# regulator_plus_switch_multi.net
KiCad netlist of a schematic drawn in EAGLE
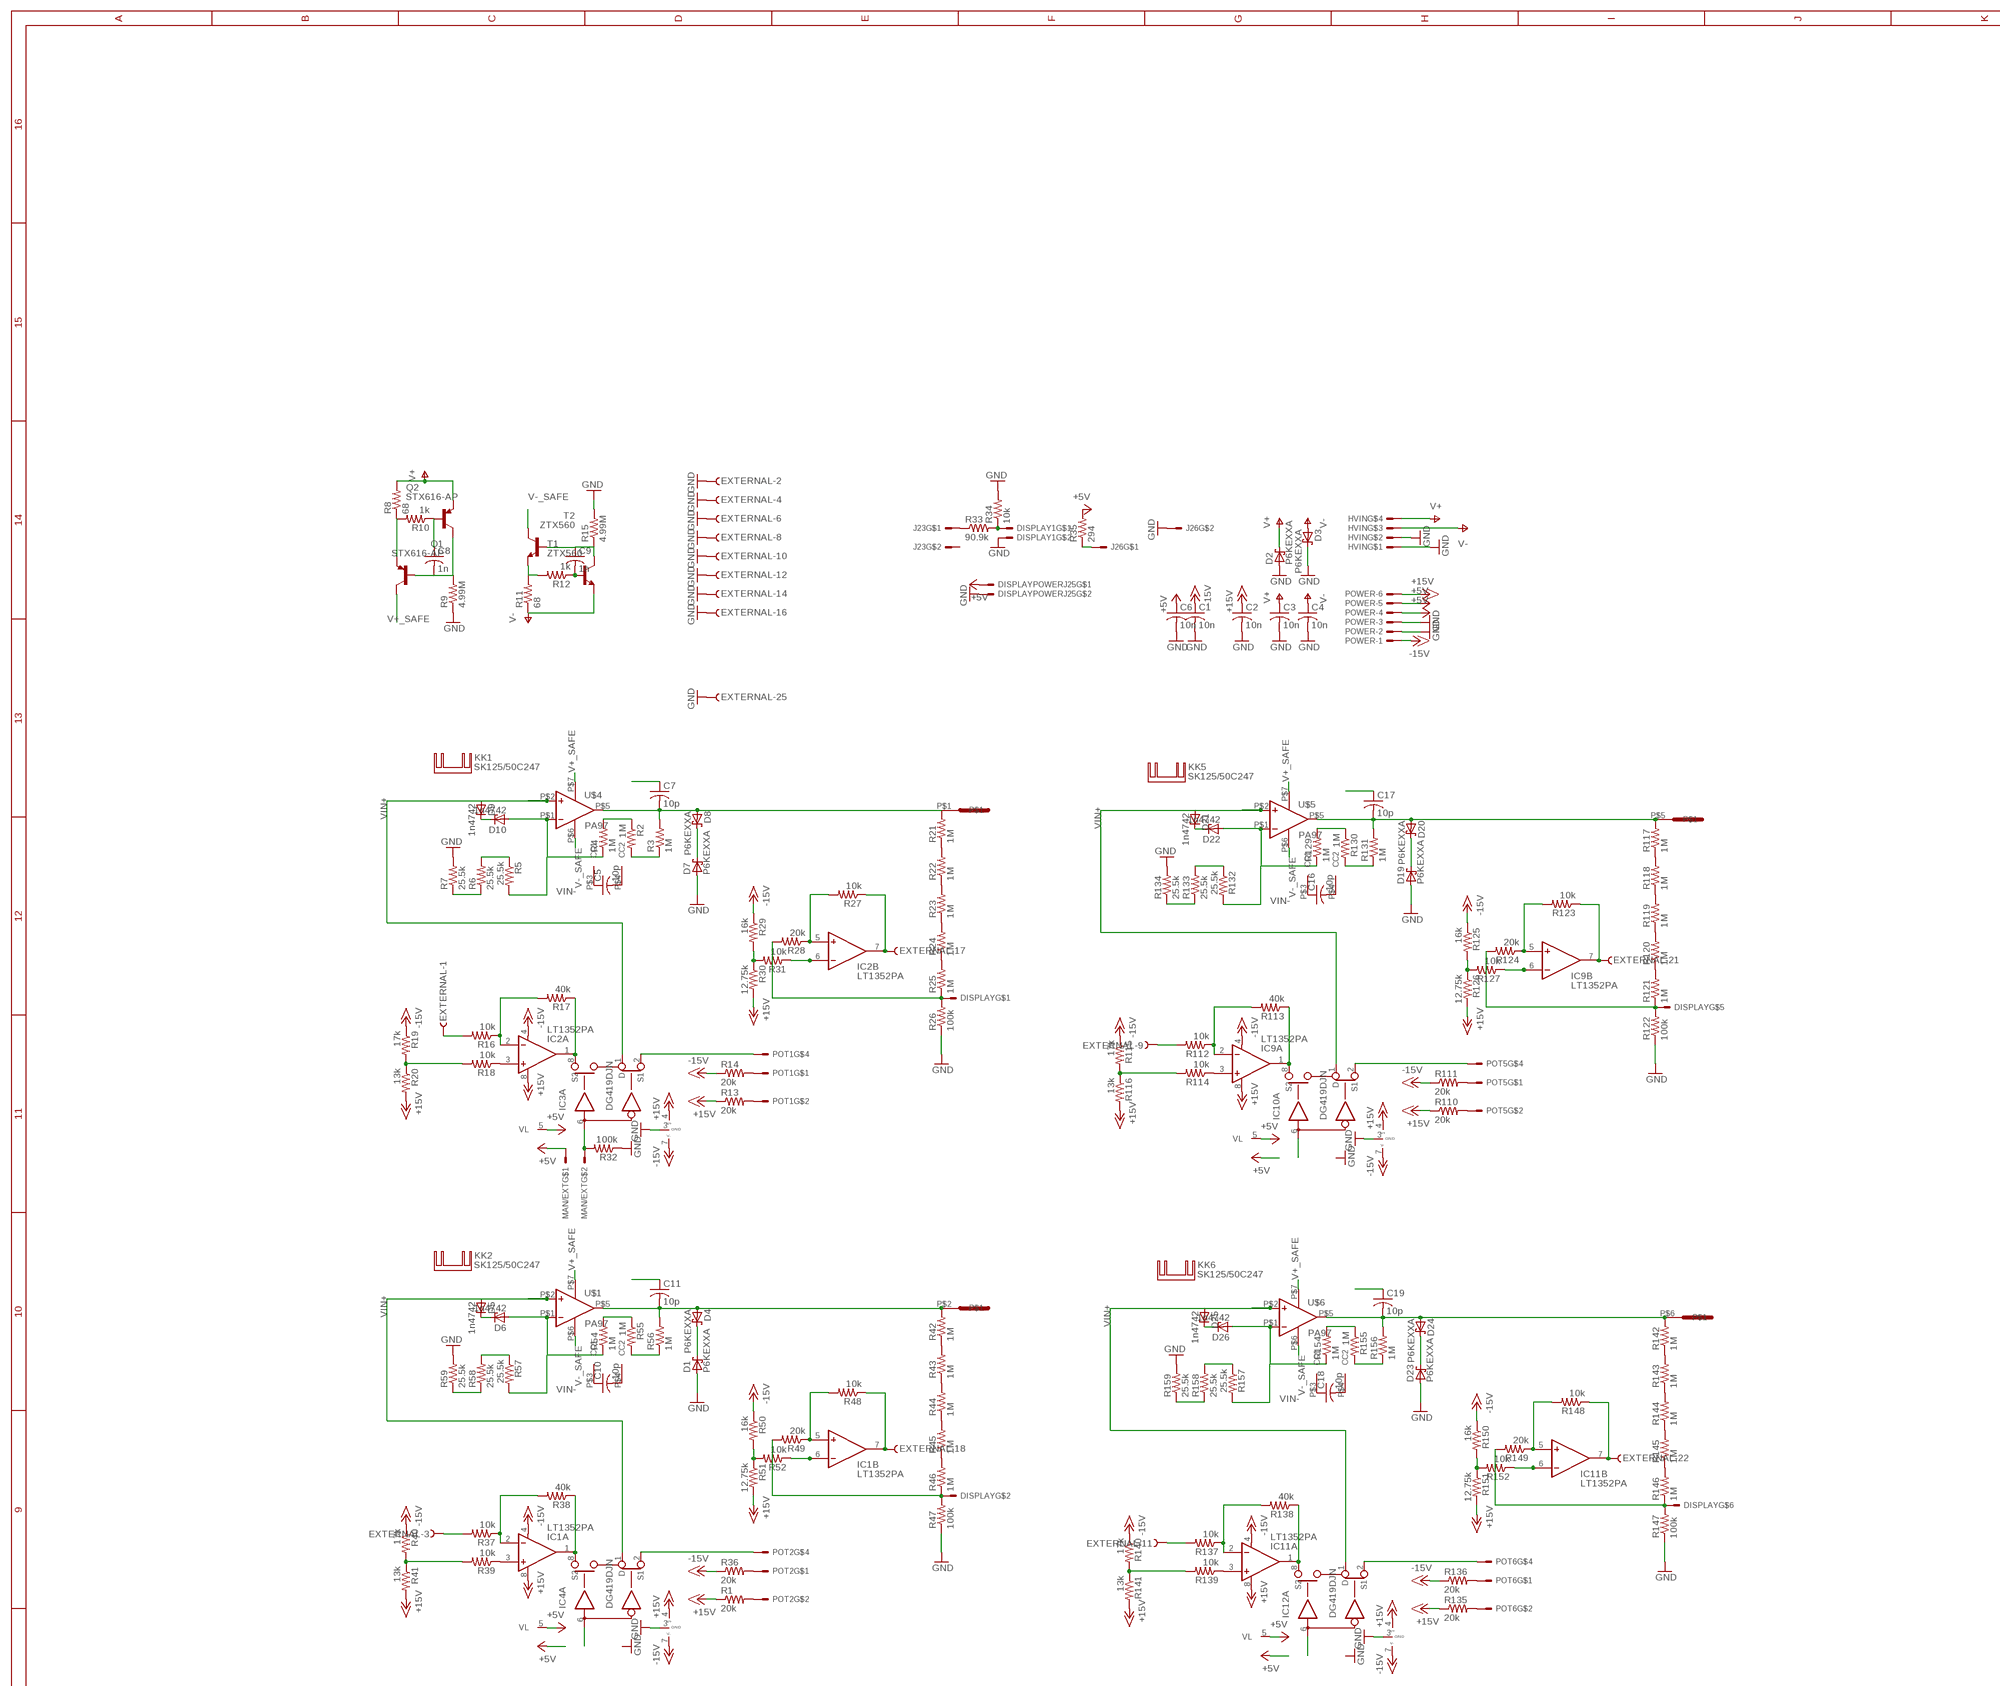
[diagram p0: schematic, sheet 1, part 1 of 2]
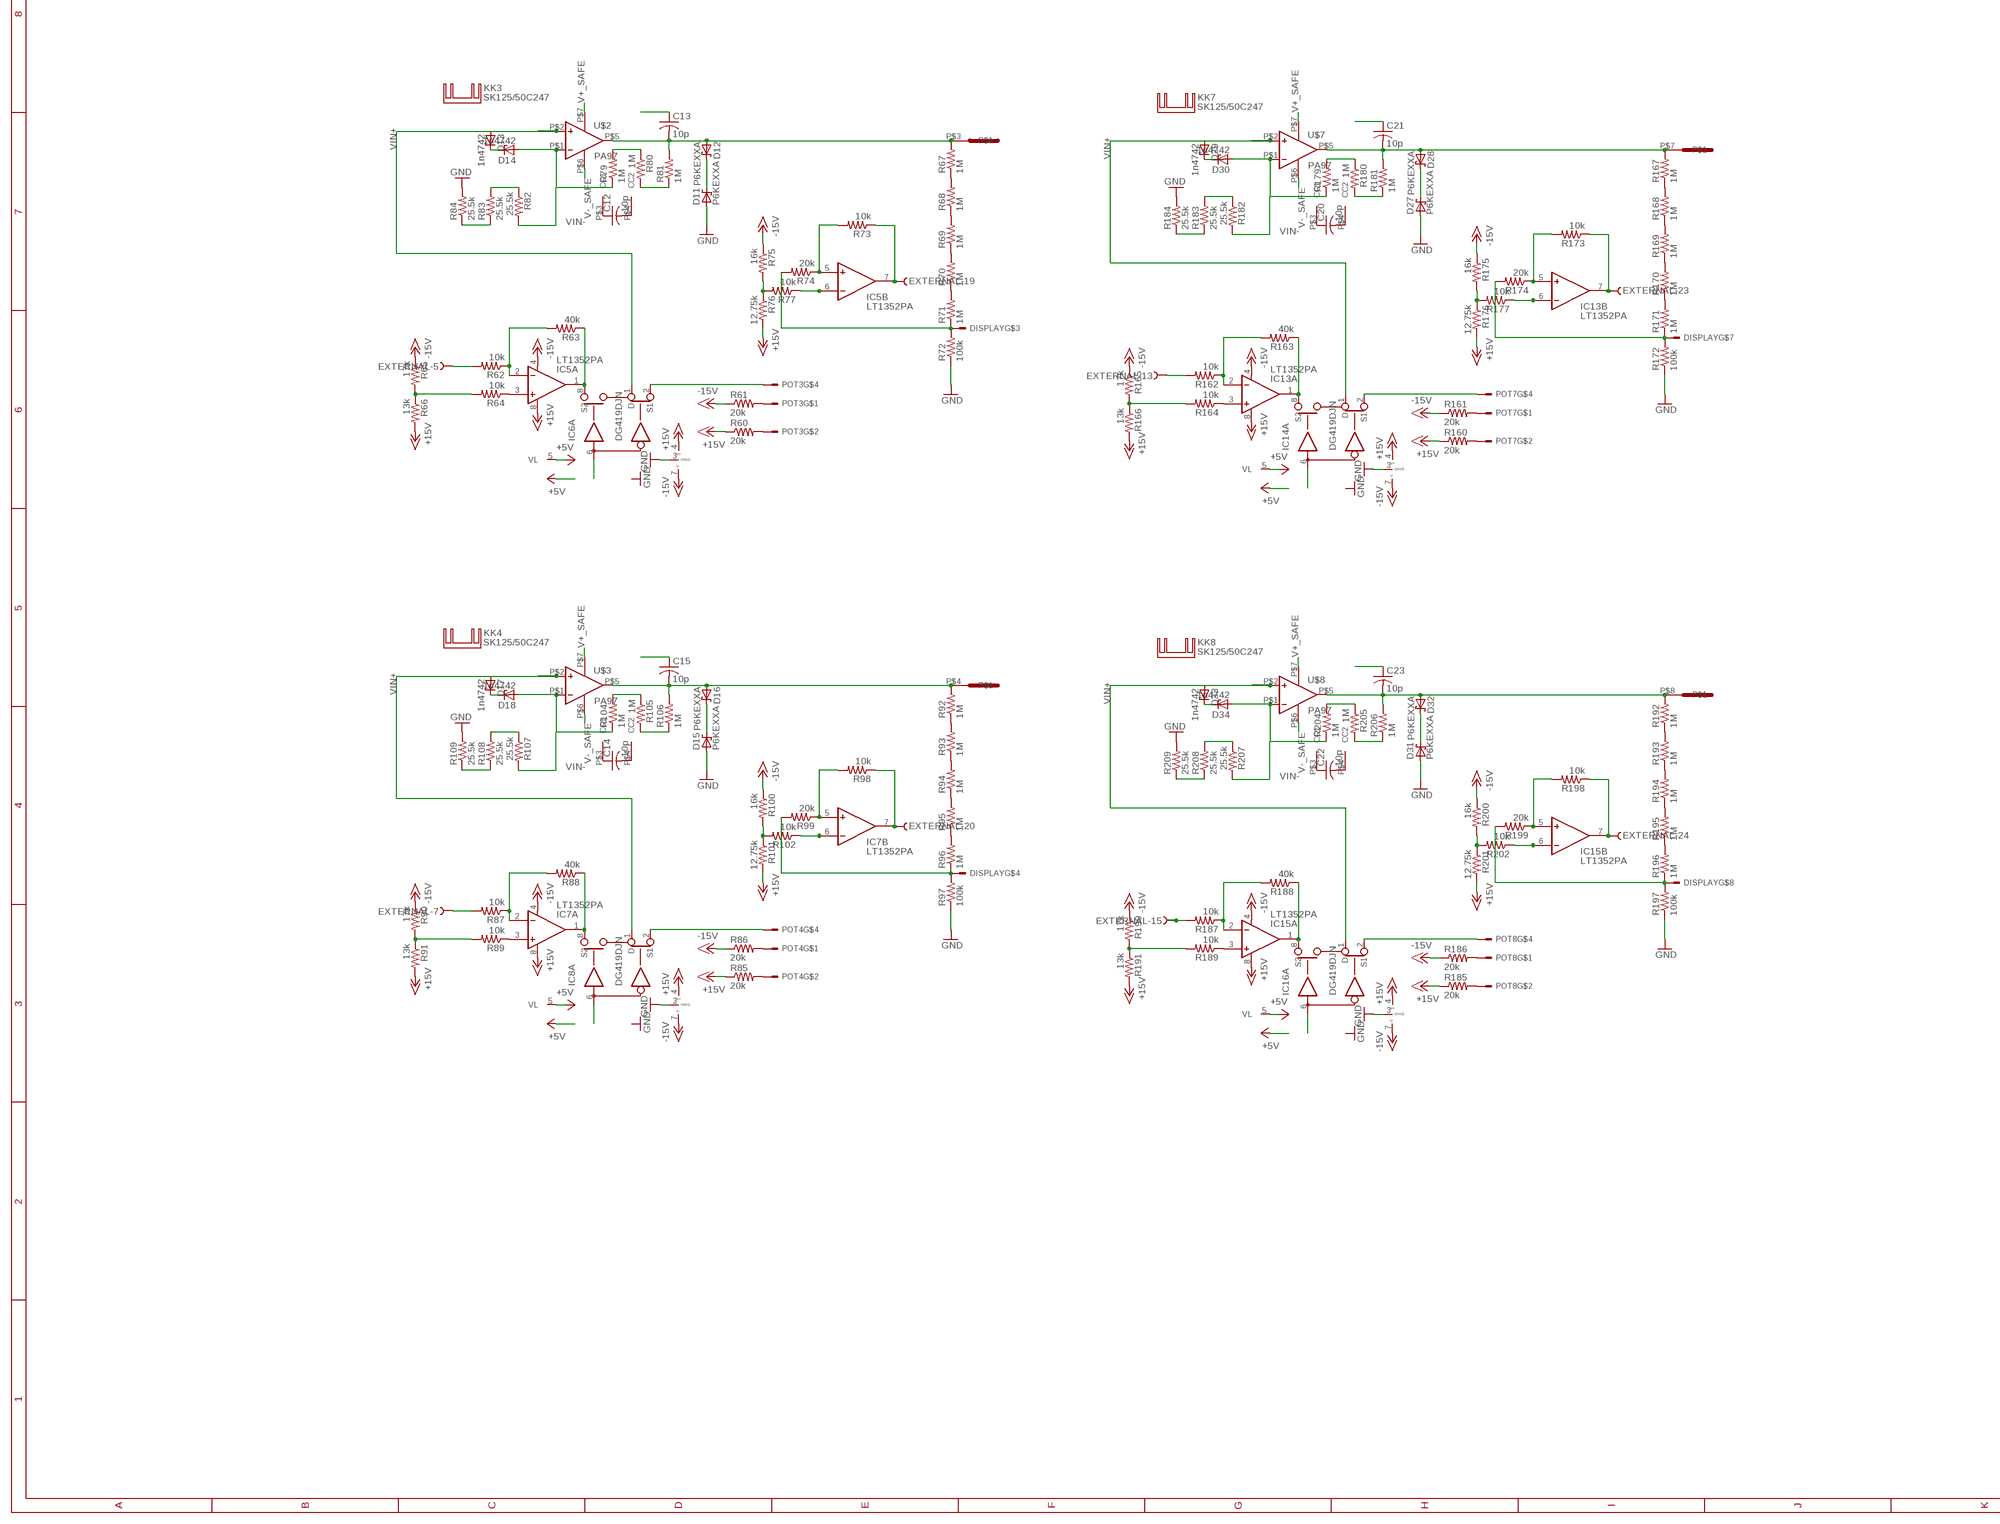
[diagram p1: schematic, sheet 1, part 2 of 2]

(export (version "E")
  (design (tool "Eeschema 10.0.6"))
  (components
    (comp (ref "C1")
      (value "10n")
      (footprint "eagle-import:C075-032X103")
      (libsource (lib "eagle-import") (part "C-US075-032X103"))
    )
    (comp (ref "C2")
      (value "10n")
      (footprint "eagle-import:C075-032X103")
      (libsource (lib "eagle-import") (part "C-US075-032X103"))
    )
    (comp (ref "C3")
      (value "10n")
      (footprint "eagle-import:C075-032X103")
      (libsource (lib "eagle-import") (part "C-US075-032X103"))
    )
    (comp (ref "C4")
      (value "10n")
      (footprint "eagle-import:C075-032X103")
      (libsource (lib "eagle-import") (part "C-US075-032X103"))
    )
    (comp (ref "C5")
      (value "10p")
      (footprint "eagle-import:C075-032X103")
      (libsource (lib "eagle-import") (part "C-US075-032X103"))
    )
    (comp (ref "C6")
      (value "10n")
      (footprint "eagle-import:C075-032X103")
      (libsource (lib "eagle-import") (part "C-US075-032X103"))
    )
    (comp (ref "C7")
      (value "10p")
      (footprint "eagle-import:C075-032X103")
      (libsource (lib "eagle-import") (part "C-US075-032X103"))
    )
    (comp (ref "C8")
      (value "1n")
      (footprint "eagle-import:C075-032X103")
      (libsource (lib "eagle-import") (part "C-US075-032X103"))
    )
    (comp (ref "C9")
      (value "1n")
      (footprint "eagle-import:C075-032X103")
      (libsource (lib "eagle-import") (part "C-US075-032X103"))
    )
    (comp (ref "C10")
      (value "10p")
      (footprint "eagle-import:C075-032X103")
      (libsource (lib "eagle-import") (part "C-US075-032X103"))
    )
    (comp (ref "C11")
      (value "10p")
      (footprint "eagle-import:C075-032X103")
      (libsource (lib "eagle-import") (part "C-US075-032X103"))
    )
    (comp (ref "C12")
      (value "10p")
      (footprint "eagle-import:C075-032X103")
      (libsource (lib "eagle-import") (part "C-US075-032X103"))
    )
    (comp (ref "C13")
      (value "10p")
      (footprint "eagle-import:C075-032X103")
      (libsource (lib "eagle-import") (part "C-US075-032X103"))
    )
    (comp (ref "C14")
      (value "10p")
      (footprint "eagle-import:C075-032X103")
      (libsource (lib "eagle-import") (part "C-US075-032X103"))
    )
    (comp (ref "C15")
      (value "10p")
      (footprint "eagle-import:C075-032X103")
      (libsource (lib "eagle-import") (part "C-US075-032X103"))
    )
    (comp (ref "C16")
      (value "10p")
      (footprint "eagle-import:C075-032X103")
      (libsource (lib "eagle-import") (part "C-US075-032X103"))
    )
    (comp (ref "C17")
      (value "10p")
      (footprint "eagle-import:C075-032X103")
      (libsource (lib "eagle-import") (part "C-US075-032X103"))
    )
    (comp (ref "C18")
      (value "10p")
      (footprint "eagle-import:C075-032X103")
      (libsource (lib "eagle-import") (part "C-US075-032X103"))
    )
    (comp (ref "C19")
      (value "10p")
      (footprint "eagle-import:C075-032X103")
      (libsource (lib "eagle-import") (part "C-US075-032X103"))
    )
    (comp (ref "C20")
      (value "10p")
      (footprint "eagle-import:C075-032X103")
      (libsource (lib "eagle-import") (part "C-US075-032X103"))
    )
    (comp (ref "C21")
      (value "10p")
      (footprint "eagle-import:C075-032X103")
      (libsource (lib "eagle-import") (part "C-US075-032X103"))
    )
    (comp (ref "C22")
      (value "10p")
      (footprint "eagle-import:C075-032X103")
      (libsource (lib "eagle-import") (part "C-US075-032X103"))
    )
    (comp (ref "C23")
      (value "10p")
      (footprint "eagle-import:C075-032X103")
      (libsource (lib "eagle-import") (part "C-US075-032X103"))
    )
    (comp (ref "D1")
      (value "P6KEXXA")
      (footprint "eagle-import:C1702-15")
      (libsource (lib "eagle-import") (part "P6KEXXA"))
    )
    (comp (ref "D2")
      (value "P6KEXXA")
      (footprint "eagle-import:C1702-15")
      (libsource (lib "eagle-import") (part "P6KEXXA"))
    )
    (comp (ref "D3")
      (value "P6KEXXA")
      (footprint "eagle-import:C1702-15")
      (libsource (lib "eagle-import") (part "P6KEXXA"))
    )
    (comp (ref "D4")
      (value "P6KEXXA")
      (footprint "eagle-import:C1702-15")
      (libsource (lib "eagle-import") (part "P6KEXXA"))
    )
    (comp (ref "D5")
      (value "1n4742")
      (footprint "eagle-import:DO41Z10")
      (libsource (lib "eagle-import") (part "ZENER-DIODEDO41Z10"))
    )
    (comp (ref "D6")
      (value "1n4742")
      (footprint "eagle-import:DO41Z10")
      (libsource (lib "eagle-import") (part "ZENER-DIODEDO41Z10"))
    )
    (comp (ref "D7")
      (value "P6KEXXA")
      (footprint "eagle-import:C1702-15")
      (libsource (lib "eagle-import") (part "P6KEXXA"))
    )
    (comp (ref "D8")
      (value "P6KEXXA")
      (footprint "eagle-import:C1702-15")
      (libsource (lib "eagle-import") (part "P6KEXXA"))
    )
    (comp (ref "D9")
      (value "1n4742")
      (footprint "eagle-import:DO41Z10")
      (libsource (lib "eagle-import") (part "ZENER-DIODEDO41Z10"))
    )
    (comp (ref "D10")
      (value "1n4742")
      (footprint "eagle-import:DO41Z10")
      (libsource (lib "eagle-import") (part "ZENER-DIODEDO41Z10"))
    )
    (comp (ref "D11")
      (value "P6KEXXA")
      (footprint "eagle-import:C1702-15")
      (libsource (lib "eagle-import") (part "P6KEXXA"))
    )
    (comp (ref "D12")
      (value "P6KEXXA")
      (footprint "eagle-import:C1702-15")
      (libsource (lib "eagle-import") (part "P6KEXXA"))
    )
    (comp (ref "D13")
      (value "1n4742")
      (footprint "eagle-import:DO41Z10")
      (libsource (lib "eagle-import") (part "ZENER-DIODEDO41Z10"))
    )
    (comp (ref "D14")
      (value "1n4742")
      (footprint "eagle-import:DO41Z10")
      (libsource (lib "eagle-import") (part "ZENER-DIODEDO41Z10"))
    )
    (comp (ref "D15")
      (value "P6KEXXA")
      (footprint "eagle-import:C1702-15")
      (libsource (lib "eagle-import") (part "P6KEXXA"))
    )
    (comp (ref "D16")
      (value "P6KEXXA")
      (footprint "eagle-import:C1702-15")
      (libsource (lib "eagle-import") (part "P6KEXXA"))
    )
    (comp (ref "D17")
      (value "1n4742")
      (footprint "eagle-import:DO41Z10")
      (libsource (lib "eagle-import") (part "ZENER-DIODEDO41Z10"))
    )
    (comp (ref "D18")
      (value "1n4742")
      (footprint "eagle-import:DO41Z10")
      (libsource (lib "eagle-import") (part "ZENER-DIODEDO41Z10"))
    )
    (comp (ref "D19")
      (value "P6KEXXA")
      (footprint "eagle-import:C1702-15")
      (libsource (lib "eagle-import") (part "P6KEXXA"))
    )
    (comp (ref "D20")
      (value "P6KEXXA")
      (footprint "eagle-import:C1702-15")
      (libsource (lib "eagle-import") (part "P6KEXXA"))
    )
    (comp (ref "D21")
      (value "1n4742")
      (footprint "eagle-import:DO41Z10")
      (libsource (lib "eagle-import") (part "ZENER-DIODEDO41Z10"))
    )
    (comp (ref "D22")
      (value "1n4742")
      (footprint "eagle-import:DO41Z10")
      (libsource (lib "eagle-import") (part "ZENER-DIODEDO41Z10"))
    )
    (comp (ref "D23")
      (value "P6KEXXA")
      (footprint "eagle-import:C1702-15")
      (libsource (lib "eagle-import") (part "P6KEXXA"))
    )
    (comp (ref "D24")
      (value "P6KEXXA")
      (footprint "eagle-import:C1702-15")
      (libsource (lib "eagle-import") (part "P6KEXXA"))
    )
    (comp (ref "D25")
      (value "1n4742")
      (footprint "eagle-import:DO41Z10")
      (libsource (lib "eagle-import") (part "ZENER-DIODEDO41Z10"))
    )
    (comp (ref "D26")
      (value "1n4742")
      (footprint "eagle-import:DO41Z10")
      (libsource (lib "eagle-import") (part "ZENER-DIODEDO41Z10"))
    )
    (comp (ref "D27")
      (value "P6KEXXA")
      (footprint "eagle-import:C1702-15")
      (libsource (lib "eagle-import") (part "P6KEXXA"))
    )
    (comp (ref "D28")
      (value "P6KEXXA")
      (footprint "eagle-import:C1702-15")
      (libsource (lib "eagle-import") (part "P6KEXXA"))
    )
    (comp (ref "D29")
      (value "1n4742")
      (footprint "eagle-import:DO41Z10")
      (libsource (lib "eagle-import") (part "ZENER-DIODEDO41Z10"))
    )
    (comp (ref "D30")
      (value "1n4742")
      (footprint "eagle-import:DO41Z10")
      (libsource (lib "eagle-import") (part "ZENER-DIODEDO41Z10"))
    )
    (comp (ref "D31")
      (value "P6KEXXA")
      (footprint "eagle-import:C1702-15")
      (libsource (lib "eagle-import") (part "P6KEXXA"))
    )
    (comp (ref "D32")
      (value "P6KEXXA")
      (footprint "eagle-import:C1702-15")
      (libsource (lib "eagle-import") (part "P6KEXXA"))
    )
    (comp (ref "D33")
      (value "1n4742")
      (footprint "eagle-import:DO41Z10")
      (libsource (lib "eagle-import") (part "ZENER-DIODEDO41Z10"))
    )
    (comp (ref "D34")
      (value "1n4742")
      (footprint "eagle-import:DO41Z10")
      (libsource (lib "eagle-import") (part "ZENER-DIODEDO41Z10"))
    )
    (comp (ref "DISPLAY")
      (value "5669-8")
      (footprint "eagle-import:5669-8")
      (libsource (lib "eagle-import") (part "5669-8"))
    )
    (comp (ref "DISPLAY1")
      (value "5569-2")
      (footprint "eagle-import:5569-2")
      (libsource (lib "eagle-import") (part "5569-2"))
    )
    (comp (ref "DISPLAYPOWERJ25")
      (value "5569-2")
      (footprint "eagle-import:5569-2")
      (libsource (lib "eagle-import") (part "5569-2"))
    )
    (comp (ref "EXTERNAL")
      (value "F25HPS")
      (footprint "eagle-import:F25HP")
      (libsource (lib "eagle-import") (part "F25?SHP"))
    )
    (comp (ref "HVIN")
      (value "5569-4")
      (footprint "eagle-import:5669-4")
      (libsource (lib "eagle-import") (part "5569-4"))
    )
    (comp (ref "IC1")
      (value "LT1352PA")
      (footprint "eagle-import:DIL08")
      (libsource (lib "eagle-import") (part "LT1352PA"))
    )
    (comp (ref "IC2")
      (value "LT1352PA")
      (footprint "eagle-import:DIL08")
      (libsource (lib "eagle-import") (part "LT1352PA"))
    )
    (comp (ref "IC3")
      (value "DG419DJN")
      (footprint "eagle-import:DIL08")
      (libsource (lib "eagle-import") (part "DG419DJN"))
    )
    (comp (ref "IC4")
      (value "DG419DJN")
      (footprint "eagle-import:DIL08")
      (libsource (lib "eagle-import") (part "DG419DJN"))
    )
    (comp (ref "IC5")
      (value "LT1352PA")
      (footprint "eagle-import:DIL08")
      (libsource (lib "eagle-import") (part "LT1352PA"))
    )
    (comp (ref "IC6")
      (value "DG419DJN")
      (footprint "eagle-import:DIL08")
      (libsource (lib "eagle-import") (part "DG419DJN"))
    )
    (comp (ref "IC7")
      (value "LT1352PA")
      (footprint "eagle-import:DIL08")
      (libsource (lib "eagle-import") (part "LT1352PA"))
    )
    (comp (ref "IC8")
      (value "DG419DJN")
      (footprint "eagle-import:DIL08")
      (libsource (lib "eagle-import") (part "DG419DJN"))
    )
    (comp (ref "IC9")
      (value "LT1352PA")
      (footprint "eagle-import:DIL08")
      (libsource (lib "eagle-import") (part "LT1352PA"))
    )
    (comp (ref "IC10")
      (value "DG419DJN")
      (footprint "eagle-import:DIL08")
      (libsource (lib "eagle-import") (part "DG419DJN"))
    )
    (comp (ref "IC11")
      (value "LT1352PA")
      (footprint "eagle-import:DIL08")
      (libsource (lib "eagle-import") (part "LT1352PA"))
    )
    (comp (ref "IC12")
      (value "DG419DJN")
      (footprint "eagle-import:DIL08")
      (libsource (lib "eagle-import") (part "DG419DJN"))
    )
    (comp (ref "IC13")
      (value "LT1352PA")
      (footprint "eagle-import:DIL08")
      (libsource (lib "eagle-import") (part "LT1352PA"))
    )
    (comp (ref "IC14")
      (value "DG419DJN")
      (footprint "eagle-import:DIL08")
      (libsource (lib "eagle-import") (part "DG419DJN"))
    )
    (comp (ref "IC15")
      (value "LT1352PA")
      (footprint "eagle-import:DIL08")
      (libsource (lib "eagle-import") (part "LT1352PA"))
    )
    (comp (ref "IC16")
      (value "DG419DJN")
      (footprint "eagle-import:DIL08")
      (libsource (lib "eagle-import") (part "DG419DJN"))
    )
    (comp (ref "J23")
      (value "5569-2")
      (footprint "eagle-import:5569-2")
      (libsource (lib "eagle-import") (part "5569-2"))
    )
    (comp (ref "J26")
      (value "5569-2")
      (footprint "eagle-import:5569-2")
      (libsource (lib "eagle-import") (part "5569-2"))
    )
    (comp (ref "KK1")
      (value "SK125/50C247")
      (footprint "eagle-import:C247-050")
      (libsource (lib "eagle-import") (part "SK125/50C247"))
    )
    (comp (ref "KK2")
      (value "SK125/50C247")
      (footprint "eagle-import:C247-050")
      (libsource (lib "eagle-import") (part "SK125/50C247"))
    )
    (comp (ref "KK3")
      (value "SK125/50C247")
      (footprint "eagle-import:C247-050")
      (libsource (lib "eagle-import") (part "SK125/50C247"))
    )
    (comp (ref "KK4")
      (value "SK125/50C247")
      (footprint "eagle-import:C247-050")
      (libsource (lib "eagle-import") (part "SK125/50C247"))
    )
    (comp (ref "KK5")
      (value "SK125/50C247")
      (footprint "eagle-import:C247-050")
      (libsource (lib "eagle-import") (part "SK125/50C247"))
    )
    (comp (ref "KK6")
      (value "SK125/50C247")
      (footprint "eagle-import:C247-050")
      (libsource (lib "eagle-import") (part "SK125/50C247"))
    )
    (comp (ref "KK7")
      (value "SK125/50C247")
      (footprint "eagle-import:C247-050")
      (libsource (lib "eagle-import") (part "SK125/50C247"))
    )
    (comp (ref "KK8")
      (value "SK125/50C247")
      (footprint "eagle-import:C247-050")
      (libsource (lib "eagle-import") (part "SK125/50C247"))
    )
    (comp (ref "MAN/EXT")
      (value "5569-2")
      (footprint "eagle-import:5569-2")
      (libsource (lib "eagle-import") (part "5569-2"))
    )
    (comp (ref "OUT")
      (value "640584-1")
      (footprint "eagle-import:640584-1")
      (libsource (lib "eagle-import") (part "640584-1"))
    )
    (comp (ref "POT1")
      (value "5569-4")
      (footprint "eagle-import:5669-4")
      (libsource (lib "eagle-import") (part "5569-4"))
    )
    (comp (ref "POT2")
      (value "5569-4")
      (footprint "eagle-import:5669-4")
      (libsource (lib "eagle-import") (part "5569-4"))
    )
    (comp (ref "POT3")
      (value "5569-4")
      (footprint "eagle-import:5669-4")
      (libsource (lib "eagle-import") (part "5569-4"))
    )
    (comp (ref "POT4")
      (value "5569-4")
      (footprint "eagle-import:5669-4")
      (libsource (lib "eagle-import") (part "5569-4"))
    )
    (comp (ref "POT5")
      (value "5569-4")
      (footprint "eagle-import:5669-4")
      (libsource (lib "eagle-import") (part "5569-4"))
    )
    (comp (ref "POT6")
      (value "5569-4")
      (footprint "eagle-import:5669-4")
      (libsource (lib "eagle-import") (part "5569-4"))
    )
    (comp (ref "POT7")
      (value "5569-4")
      (footprint "eagle-import:5669-4")
      (libsource (lib "eagle-import") (part "5569-4"))
    )
    (comp (ref "POT8")
      (value "5569-4")
      (footprint "eagle-import:5669-4")
      (libsource (lib "eagle-import") (part "5569-4"))
    )
    (comp (ref "POWER")
      (value "KK-156-6")
      (footprint "eagle-import:KK-156-6")
      (libsource (lib "eagle-import") (part "KK-156-6"))
    )
    (comp (ref "Q1")
      (value "STX616-AP")
      (footprint "eagle-import:TO92")
      (libsource (lib "eagle-import") (part "2N3906"))
    )
    (comp (ref "Q2")
      (value "STX616-AP")
      (footprint "eagle-import:TO92")
      (libsource (lib "eagle-import") (part "2N3906"))
    )
    (comp (ref "R1")
      (value "20k")
      (footprint "eagle-import:0207_10")
      (libsource (lib "eagle-import") (part "R-US_0207/10"))
    )
    (comp (ref "R2")
      (value "1M")
      (footprint "eagle-import:0207_10")
      (libsource (lib "eagle-import") (part "R-US_0207/10"))
    )
    (comp (ref "R3")
      (value "1M")
      (footprint "eagle-import:0207_10")
      (libsource (lib "eagle-import") (part "R-US_0207/10"))
    )
    (comp (ref "R4")
      (value "1M")
      (footprint "eagle-import:0207_10")
      (libsource (lib "eagle-import") (part "R-US_0207/10"))
    )
    (comp (ref "R5")
      (value "25.5k")
      (footprint "eagle-import:0207_10")
      (libsource (lib "eagle-import") (part "R-US_0207/10"))
    )
    (comp (ref "R6")
      (value "25.5k")
      (footprint "eagle-import:0207_10")
      (libsource (lib "eagle-import") (part "R-US_0207/10"))
    )
    (comp (ref "R7")
      (value "25.5k")
      (footprint "eagle-import:0207_10")
      (libsource (lib "eagle-import") (part "R-US_0207/10"))
    )
    (comp (ref "R8")
      (value "68")
      (footprint "eagle-import:0207_10")
      (libsource (lib "eagle-import") (part "R-US_0207/10"))
    )
    (comp (ref "R9")
      (value "4.99M")
      (footprint "eagle-import:0207_10")
      (libsource (lib "eagle-import") (part "R-US_0207/10"))
    )
    (comp (ref "R10")
      (value "1k")
      (footprint "eagle-import:0207_10")
      (libsource (lib "eagle-import") (part "R-US_0207/10"))
    )
    (comp (ref "R11")
      (value "68")
      (footprint "eagle-import:0207_10")
      (libsource (lib "eagle-import") (part "R-US_0207/10"))
    )
    (comp (ref "R12")
      (value "1k")
      (footprint "eagle-import:0207_10")
      (libsource (lib "eagle-import") (part "R-US_0207/10"))
    )
    (comp (ref "R13")
      (value "20k")
      (footprint "eagle-import:0207_10")
      (libsource (lib "eagle-import") (part "R-US_0207/10"))
    )
    (comp (ref "R14")
      (value "20k")
      (footprint "eagle-import:0207_10")
      (libsource (lib "eagle-import") (part "R-US_0207/10"))
    )
    (comp (ref "R15")
      (value "4.99M")
      (footprint "eagle-import:0207_10")
      (libsource (lib "eagle-import") (part "R-US_0207/10"))
    )
    (comp (ref "R16")
      (value "10k")
      (footprint "eagle-import:0207_10")
      (libsource (lib "eagle-import") (part "R-US_0207/10"))
    )
    (comp (ref "R17")
      (value "40k")
      (footprint "eagle-import:0207_10")
      (libsource (lib "eagle-import") (part "R-US_0207/10"))
    )
    (comp (ref "R18")
      (value "10k")
      (footprint "eagle-import:0207_10")
      (libsource (lib "eagle-import") (part "R-US_0207/10"))
    )
    (comp (ref "R19")
      (value "17k")
      (footprint "eagle-import:0207_10")
      (libsource (lib "eagle-import") (part "R-US_0207/10"))
    )
    (comp (ref "R20")
      (value "13k")
      (footprint "eagle-import:0207_10")
      (libsource (lib "eagle-import") (part "R-US_0207/10"))
    )
    (comp (ref "R21")
      (value "1M")
      (footprint "eagle-import:0207_10")
      (libsource (lib "eagle-import") (part "resistor_R-US_0207/10"))
    )
    (comp (ref "R22")
      (value "1M")
      (footprint "eagle-import:0207_10")
      (libsource (lib "eagle-import") (part "resistor_R-US_0207/10"))
    )
    (comp (ref "R23")
      (value "1M")
      (footprint "eagle-import:0207_10")
      (libsource (lib "eagle-import") (part "resistor_R-US_0207/10"))
    )
    (comp (ref "R24")
      (value "1M")
      (footprint "eagle-import:0207_10")
      (libsource (lib "eagle-import") (part "resistor_R-US_0207/10"))
    )
    (comp (ref "R25")
      (value "1M")
      (footprint "eagle-import:0207_10")
      (libsource (lib "eagle-import") (part "resistor_R-US_0207/10"))
    )
    (comp (ref "R26")
      (value "100k")
      (footprint "eagle-import:0207_10")
      (libsource (lib "eagle-import") (part "R-US_0207/10"))
    )
    (comp (ref "R27")
      (value "10k")
      (footprint "eagle-import:0207_10")
      (libsource (lib "eagle-import") (part "R-US_0207/10"))
    )
    (comp (ref "R28")
      (value "20k")
      (footprint "eagle-import:0207_10")
      (libsource (lib "eagle-import") (part "R-US_0207/10"))
    )
    (comp (ref "R29")
      (value "16k")
      (footprint "eagle-import:0207_10")
      (libsource (lib "eagle-import") (part "R-US_0207/10"))
    )
    (comp (ref "R30")
      (value "12.75k")
      (footprint "eagle-import:0207_10")
      (libsource (lib "eagle-import") (part "R-US_0207/10"))
    )
    (comp (ref "R31")
      (value "10k")
      (footprint "eagle-import:0207_10")
      (libsource (lib "eagle-import") (part "R-US_0207/10"))
    )
    (comp (ref "R32")
      (value "100k")
      (footprint "eagle-import:0207_10")
      (libsource (lib "eagle-import") (part "R-US_0207/10"))
    )
    (comp (ref "R33")
      (value "90.9k")
      (footprint "eagle-import:0207_10")
      (libsource (lib "eagle-import") (part "R-US_0207/10"))
    )
    (comp (ref "R34")
      (value "10k")
      (footprint "eagle-import:0207_10")
      (libsource (lib "eagle-import") (part "R-US_0207/10"))
    )
    (comp (ref "R35")
      (value "294")
      (footprint "eagle-import:0207_10")
      (libsource (lib "eagle-import") (part "R-US_0207/10"))
    )
    (comp (ref "R36")
      (value "20k")
      (footprint "eagle-import:0207_10")
      (libsource (lib "eagle-import") (part "R-US_0207/10"))
    )
    (comp (ref "R37")
      (value "10k")
      (footprint "eagle-import:0207_10")
      (libsource (lib "eagle-import") (part "R-US_0207/10"))
    )
    (comp (ref "R38")
      (value "40k")
      (footprint "eagle-import:0207_10")
      (libsource (lib "eagle-import") (part "R-US_0207/10"))
    )
    (comp (ref "R39")
      (value "10k")
      (footprint "eagle-import:0207_10")
      (libsource (lib "eagle-import") (part "R-US_0207/10"))
    )
    (comp (ref "R40")
      (value "17k")
      (footprint "eagle-import:0207_10")
      (libsource (lib "eagle-import") (part "R-US_0207/10"))
    )
    (comp (ref "R41")
      (value "13k")
      (footprint "eagle-import:0207_10")
      (libsource (lib "eagle-import") (part "R-US_0207/10"))
    )
    (comp (ref "R42")
      (value "1M")
      (footprint "eagle-import:0207_10")
      (libsource (lib "eagle-import") (part "resistor_R-US_0207/10"))
    )
    (comp (ref "R43")
      (value "1M")
      (footprint "eagle-import:0207_10")
      (libsource (lib "eagle-import") (part "resistor_R-US_0207/10"))
    )
    (comp (ref "R44")
      (value "1M")
      (footprint "eagle-import:0207_10")
      (libsource (lib "eagle-import") (part "resistor_R-US_0207/10"))
    )
    (comp (ref "R45")
      (value "1M")
      (footprint "eagle-import:0207_10")
      (libsource (lib "eagle-import") (part "resistor_R-US_0207/10"))
    )
    (comp (ref "R46")
      (value "1M")
      (footprint "eagle-import:0207_10")
      (libsource (lib "eagle-import") (part "resistor_R-US_0207/10"))
    )
    (comp (ref "R47")
      (value "100k")
      (footprint "eagle-import:0207_10")
      (libsource (lib "eagle-import") (part "R-US_0207/10"))
    )
    (comp (ref "R48")
      (value "10k")
      (footprint "eagle-import:0207_10")
      (libsource (lib "eagle-import") (part "R-US_0207/10"))
    )
    (comp (ref "R49")
      (value "20k")
      (footprint "eagle-import:0207_10")
      (libsource (lib "eagle-import") (part "R-US_0207/10"))
    )
    (comp (ref "R50")
      (value "16k")
      (footprint "eagle-import:0207_10")
      (libsource (lib "eagle-import") (part "R-US_0207/10"))
    )
    (comp (ref "R51")
      (value "12.75k")
      (footprint "eagle-import:0207_10")
      (libsource (lib "eagle-import") (part "R-US_0207/10"))
    )
    (comp (ref "R52")
      (value "10k")
      (footprint "eagle-import:0207_10")
      (libsource (lib "eagle-import") (part "R-US_0207/10"))
    )
    (comp (ref "R54")
      (value "1M")
      (footprint "eagle-import:0207_10")
      (libsource (lib "eagle-import") (part "R-US_0207/10"))
    )
    (comp (ref "R55")
      (value "1M")
      (footprint "eagle-import:0207_10")
      (libsource (lib "eagle-import") (part "R-US_0207/10"))
    )
    (comp (ref "R56")
      (value "1M")
      (footprint "eagle-import:0207_10")
      (libsource (lib "eagle-import") (part "R-US_0207/10"))
    )
    (comp (ref "R57")
      (value "25.5k")
      (footprint "eagle-import:0207_10")
      (libsource (lib "eagle-import") (part "R-US_0207/10"))
    )
    (comp (ref "R58")
      (value "25.5k")
      (footprint "eagle-import:0207_10")
      (libsource (lib "eagle-import") (part "R-US_0207/10"))
    )
    (comp (ref "R59")
      (value "25.5k")
      (footprint "eagle-import:0207_10")
      (libsource (lib "eagle-import") (part "R-US_0207/10"))
    )
    (comp (ref "R60")
      (value "20k")
      (footprint "eagle-import:0207_10")
      (libsource (lib "eagle-import") (part "R-US_0207/10"))
    )
    (comp (ref "R61")
      (value "20k")
      (footprint "eagle-import:0207_10")
      (libsource (lib "eagle-import") (part "R-US_0207/10"))
    )
    (comp (ref "R62")
      (value "10k")
      (footprint "eagle-import:0207_10")
      (libsource (lib "eagle-import") (part "R-US_0207/10"))
    )
    (comp (ref "R63")
      (value "40k")
      (footprint "eagle-import:0207_10")
      (libsource (lib "eagle-import") (part "R-US_0207/10"))
    )
    (comp (ref "R64")
      (value "10k")
      (footprint "eagle-import:0207_10")
      (libsource (lib "eagle-import") (part "R-US_0207/10"))
    )
    (comp (ref "R65")
      (value "17k")
      (footprint "eagle-import:0207_10")
      (libsource (lib "eagle-import") (part "R-US_0207/10"))
    )
    (comp (ref "R66")
      (value "13k")
      (footprint "eagle-import:0207_10")
      (libsource (lib "eagle-import") (part "R-US_0207/10"))
    )
    (comp (ref "R67")
      (value "1M")
      (footprint "eagle-import:0207_10")
      (libsource (lib "eagle-import") (part "resistor_R-US_0207/10"))
    )
    (comp (ref "R68")
      (value "1M")
      (footprint "eagle-import:0207_10")
      (libsource (lib "eagle-import") (part "resistor_R-US_0207/10"))
    )
    (comp (ref "R69")
      (value "1M")
      (footprint "eagle-import:0207_10")
      (libsource (lib "eagle-import") (part "resistor_R-US_0207/10"))
    )
    (comp (ref "R70")
      (value "1M")
      (footprint "eagle-import:0207_10")
      (libsource (lib "eagle-import") (part "resistor_R-US_0207/10"))
    )
    (comp (ref "R71")
      (value "1M")
      (footprint "eagle-import:0207_10")
      (libsource (lib "eagle-import") (part "resistor_R-US_0207/10"))
    )
    (comp (ref "R72")
      (value "100k")
      (footprint "eagle-import:0207_10")
      (libsource (lib "eagle-import") (part "R-US_0207/10"))
    )
    (comp (ref "R73")
      (value "10k")
      (footprint "eagle-import:0207_10")
      (libsource (lib "eagle-import") (part "R-US_0207/10"))
    )
    (comp (ref "R74")
      (value "20k")
      (footprint "eagle-import:0207_10")
      (libsource (lib "eagle-import") (part "R-US_0207/10"))
    )
    (comp (ref "R75")
      (value "16k")
      (footprint "eagle-import:0207_10")
      (libsource (lib "eagle-import") (part "R-US_0207/10"))
    )
    (comp (ref "R76")
      (value "12.75k")
      (footprint "eagle-import:0207_10")
      (libsource (lib "eagle-import") (part "R-US_0207/10"))
    )
    (comp (ref "R77")
      (value "10k")
      (footprint "eagle-import:0207_10")
      (libsource (lib "eagle-import") (part "R-US_0207/10"))
    )
    (comp (ref "R79")
      (value "1M")
      (footprint "eagle-import:0207_10")
      (libsource (lib "eagle-import") (part "R-US_0207/10"))
    )
    (comp (ref "R80")
      (value "1M")
      (footprint "eagle-import:0207_10")
      (libsource (lib "eagle-import") (part "R-US_0207/10"))
    )
    (comp (ref "R81")
      (value "1M")
      (footprint "eagle-import:0207_10")
      (libsource (lib "eagle-import") (part "R-US_0207/10"))
    )
    (comp (ref "R82")
      (value "25.5k")
      (footprint "eagle-import:0207_10")
      (libsource (lib "eagle-import") (part "R-US_0207/10"))
    )
    (comp (ref "R83")
      (value "25.5k")
      (footprint "eagle-import:0207_10")
      (libsource (lib "eagle-import") (part "R-US_0207/10"))
    )
    (comp (ref "R84")
      (value "25.5k")
      (footprint "eagle-import:0207_10")
      (libsource (lib "eagle-import") (part "R-US_0207/10"))
    )
    (comp (ref "R85")
      (value "20k")
      (footprint "eagle-import:0207_10")
      (libsource (lib "eagle-import") (part "R-US_0207/10"))
    )
    (comp (ref "R86")
      (value "20k")
      (footprint "eagle-import:0207_10")
      (libsource (lib "eagle-import") (part "R-US_0207/10"))
    )
    (comp (ref "R87")
      (value "10k")
      (footprint "eagle-import:0207_10")
      (libsource (lib "eagle-import") (part "R-US_0207/10"))
    )
    (comp (ref "R88")
      (value "40k")
      (footprint "eagle-import:0207_10")
      (libsource (lib "eagle-import") (part "R-US_0207/10"))
    )
    (comp (ref "R89")
      (value "10k")
      (footprint "eagle-import:0207_10")
      (libsource (lib "eagle-import") (part "R-US_0207/10"))
    )
    (comp (ref "R90")
      (value "17k")
      (footprint "eagle-import:0207_10")
      (libsource (lib "eagle-import") (part "R-US_0207/10"))
    )
    (comp (ref "R91")
      (value "13k")
      (footprint "eagle-import:0207_10")
      (libsource (lib "eagle-import") (part "R-US_0207/10"))
    )
    (comp (ref "R92")
      (value "1M")
      (footprint "eagle-import:0207_10")
      (libsource (lib "eagle-import") (part "resistor_R-US_0207/10"))
    )
    (comp (ref "R93")
      (value "1M")
      (footprint "eagle-import:0207_10")
      (libsource (lib "eagle-import") (part "resistor_R-US_0207/10"))
    )
    (comp (ref "R94")
      (value "1M")
      (footprint "eagle-import:0207_10")
      (libsource (lib "eagle-import") (part "resistor_R-US_0207/10"))
    )
    (comp (ref "R95")
      (value "1M")
      (footprint "eagle-import:0207_10")
      (libsource (lib "eagle-import") (part "resistor_R-US_0207/10"))
    )
    (comp (ref "R96")
      (value "1M")
      (footprint "eagle-import:0207_10")
      (libsource (lib "eagle-import") (part "resistor_R-US_0207/10"))
    )
    (comp (ref "R97")
      (value "100k")
      (footprint "eagle-import:0207_10")
      (libsource (lib "eagle-import") (part "R-US_0207/10"))
    )
    (comp (ref "R98")
      (value "10k")
      (footprint "eagle-import:0207_10")
      (libsource (lib "eagle-import") (part "R-US_0207/10"))
    )
    (comp (ref "R99")
      (value "20k")
      (footprint "eagle-import:0207_10")
      (libsource (lib "eagle-import") (part "R-US_0207/10"))
    )
    (comp (ref "R100")
      (value "16k")
      (footprint "eagle-import:0207_10")
      (libsource (lib "eagle-import") (part "R-US_0207/10"))
    )
    (comp (ref "R101")
      (value "12.75k")
      (footprint "eagle-import:0207_10")
      (libsource (lib "eagle-import") (part "R-US_0207/10"))
    )
    (comp (ref "R102")
      (value "10k")
      (footprint "eagle-import:0207_10")
      (libsource (lib "eagle-import") (part "R-US_0207/10"))
    )
    (comp (ref "R104")
      (value "1M")
      (footprint "eagle-import:0207_10")
      (libsource (lib "eagle-import") (part "R-US_0207/10"))
    )
    (comp (ref "R105")
      (value "1M")
      (footprint "eagle-import:0207_10")
      (libsource (lib "eagle-import") (part "R-US_0207/10"))
    )
    (comp (ref "R106")
      (value "1M")
      (footprint "eagle-import:0207_10")
      (libsource (lib "eagle-import") (part "R-US_0207/10"))
    )
    (comp (ref "R107")
      (value "25.5k")
      (footprint "eagle-import:0207_10")
      (libsource (lib "eagle-import") (part "R-US_0207/10"))
    )
    (comp (ref "R108")
      (value "25.5k")
      (footprint "eagle-import:0207_10")
      (libsource (lib "eagle-import") (part "R-US_0207/10"))
    )
    (comp (ref "R109")
      (value "25.5k")
      (footprint "eagle-import:0207_10")
      (libsource (lib "eagle-import") (part "R-US_0207/10"))
    )
    (comp (ref "R110")
      (value "20k")
      (footprint "eagle-import:0207_10")
      (libsource (lib "eagle-import") (part "R-US_0207/10"))
    )
    (comp (ref "R111")
      (value "20k")
      (footprint "eagle-import:0207_10")
      (libsource (lib "eagle-import") (part "R-US_0207/10"))
    )
    (comp (ref "R112")
      (value "10k")
      (footprint "eagle-import:0207_10")
      (libsource (lib "eagle-import") (part "R-US_0207/10"))
    )
    (comp (ref "R113")
      (value "40k")
      (footprint "eagle-import:0207_10")
      (libsource (lib "eagle-import") (part "R-US_0207/10"))
    )
    (comp (ref "R114")
      (value "10k")
      (footprint "eagle-import:0207_10")
      (libsource (lib "eagle-import") (part "R-US_0207/10"))
    )
    (comp (ref "R115")
      (value "17k")
      (footprint "eagle-import:0207_10")
      (libsource (lib "eagle-import") (part "R-US_0207/10"))
    )
    (comp (ref "R116")
      (value "13k")
      (footprint "eagle-import:0207_10")
      (libsource (lib "eagle-import") (part "R-US_0207/10"))
    )
    (comp (ref "R117")
      (value "1M")
      (footprint "eagle-import:0207_10")
      (libsource (lib "eagle-import") (part "resistor_R-US_0207/10"))
    )
    (comp (ref "R118")
      (value "1M")
      (footprint "eagle-import:0207_10")
      (libsource (lib "eagle-import") (part "resistor_R-US_0207/10"))
    )
    (comp (ref "R119")
      (value "1M")
      (footprint "eagle-import:0207_10")
      (libsource (lib "eagle-import") (part "resistor_R-US_0207/10"))
    )
    (comp (ref "R120")
      (value "1M")
      (footprint "eagle-import:0207_10")
      (libsource (lib "eagle-import") (part "resistor_R-US_0207/10"))
    )
    (comp (ref "R121")
      (value "1M")
      (footprint "eagle-import:0207_10")
      (libsource (lib "eagle-import") (part "resistor_R-US_0207/10"))
    )
    (comp (ref "R122")
      (value "100k")
      (footprint "eagle-import:0207_10")
      (libsource (lib "eagle-import") (part "R-US_0207/10"))
    )
    (comp (ref "R123")
      (value "10k")
      (footprint "eagle-import:0207_10")
      (libsource (lib "eagle-import") (part "R-US_0207/10"))
    )
    (comp (ref "R124")
      (value "20k")
      (footprint "eagle-import:0207_10")
      (libsource (lib "eagle-import") (part "R-US_0207/10"))
    )
    (comp (ref "R125")
      (value "16k")
      (footprint "eagle-import:0207_10")
      (libsource (lib "eagle-import") (part "R-US_0207/10"))
    )
    (comp (ref "R126")
      (value "12.75k")
      (footprint "eagle-import:0207_10")
      (libsource (lib "eagle-import") (part "R-US_0207/10"))
    )
    (comp (ref "R127")
      (value "10k")
      (footprint "eagle-import:0207_10")
      (libsource (lib "eagle-import") (part "R-US_0207/10"))
    )
    (comp (ref "R129")
      (value "1M")
      (footprint "eagle-import:0207_10")
      (libsource (lib "eagle-import") (part "R-US_0207/10"))
    )
    (comp (ref "R130")
      (value "1M")
      (footprint "eagle-import:0207_10")
      (libsource (lib "eagle-import") (part "R-US_0207/10"))
    )
    (comp (ref "R131")
      (value "1M")
      (footprint "eagle-import:0207_10")
      (libsource (lib "eagle-import") (part "R-US_0207/10"))
    )
    (comp (ref "R132")
      (value "25.5k")
      (footprint "eagle-import:0207_10")
      (libsource (lib "eagle-import") (part "R-US_0207/10"))
    )
    (comp (ref "R133")
      (value "25.5k")
      (footprint "eagle-import:0207_10")
      (libsource (lib "eagle-import") (part "R-US_0207/10"))
    )
    (comp (ref "R134")
      (value "25.5k")
      (footprint "eagle-import:0207_10")
      (libsource (lib "eagle-import") (part "R-US_0207/10"))
    )
    (comp (ref "R135")
      (value "20k")
      (footprint "eagle-import:0207_10")
      (libsource (lib "eagle-import") (part "R-US_0207/10"))
    )
    (comp (ref "R136")
      (value "20k")
      (footprint "eagle-import:0207_10")
      (libsource (lib "eagle-import") (part "R-US_0207/10"))
    )
    (comp (ref "R137")
      (value "10k")
      (footprint "eagle-import:0207_10")
      (libsource (lib "eagle-import") (part "R-US_0207/10"))
    )
    (comp (ref "R138")
      (value "40k")
      (footprint "eagle-import:0207_10")
      (libsource (lib "eagle-import") (part "R-US_0207/10"))
    )
    (comp (ref "R139")
      (value "10k")
      (footprint "eagle-import:0207_10")
      (libsource (lib "eagle-import") (part "R-US_0207/10"))
    )
    (comp (ref "R140")
      (value "17k")
      (footprint "eagle-import:0207_10")
      (libsource (lib "eagle-import") (part "R-US_0207/10"))
    )
    (comp (ref "R141")
      (value "13k")
      (footprint "eagle-import:0207_10")
      (libsource (lib "eagle-import") (part "R-US_0207/10"))
    )
    (comp (ref "R142")
      (value "1M")
      (footprint "eagle-import:0207_10")
      (libsource (lib "eagle-import") (part "resistor_R-US_0207/10"))
    )
    (comp (ref "R143")
      (value "1M")
      (footprint "eagle-import:0207_10")
      (libsource (lib "eagle-import") (part "resistor_R-US_0207/10"))
    )
    (comp (ref "R144")
      (value "1M")
      (footprint "eagle-import:0207_10")
      (libsource (lib "eagle-import") (part "resistor_R-US_0207/10"))
    )
    (comp (ref "R145")
      (value "1M")
      (footprint "eagle-import:0207_10")
      (libsource (lib "eagle-import") (part "resistor_R-US_0207/10"))
    )
    (comp (ref "R146")
      (value "1M")
      (footprint "eagle-import:0207_10")
      (libsource (lib "eagle-import") (part "resistor_R-US_0207/10"))
    )
    (comp (ref "R147")
      (value "100k")
      (footprint "eagle-import:0207_10")
      (libsource (lib "eagle-import") (part "R-US_0207/10"))
    )
    (comp (ref "R148")
      (value "10k")
      (footprint "eagle-import:0207_10")
      (libsource (lib "eagle-import") (part "R-US_0207/10"))
    )
    (comp (ref "R149")
      (value "20k")
      (footprint "eagle-import:0207_10")
      (libsource (lib "eagle-import") (part "R-US_0207/10"))
    )
    (comp (ref "R150")
      (value "16k")
      (footprint "eagle-import:0207_10")
      (libsource (lib "eagle-import") (part "R-US_0207/10"))
    )
    (comp (ref "R151")
      (value "12.75k")
      (footprint "eagle-import:0207_10")
      (libsource (lib "eagle-import") (part "R-US_0207/10"))
    )
    (comp (ref "R152")
      (value "10k")
      (footprint "eagle-import:0207_10")
      (libsource (lib "eagle-import") (part "R-US_0207/10"))
    )
    (comp (ref "R154")
      (value "1M")
      (footprint "eagle-import:0207_10")
      (libsource (lib "eagle-import") (part "R-US_0207/10"))
    )
    (comp (ref "R155")
      (value "1M")
      (footprint "eagle-import:0207_10")
      (libsource (lib "eagle-import") (part "R-US_0207/10"))
    )
    (comp (ref "R156")
      (value "1M")
      (footprint "eagle-import:0207_10")
      (libsource (lib "eagle-import") (part "R-US_0207/10"))
    )
    (comp (ref "R157")
      (value "25.5k")
      (footprint "eagle-import:0207_10")
      (libsource (lib "eagle-import") (part "R-US_0207/10"))
    )
    (comp (ref "R158")
      (value "25.5k")
      (footprint "eagle-import:0207_10")
      (libsource (lib "eagle-import") (part "R-US_0207/10"))
    )
    (comp (ref "R159")
      (value "25.5k")
      (footprint "eagle-import:0207_10")
      (libsource (lib "eagle-import") (part "R-US_0207/10"))
    )
    (comp (ref "R160")
      (value "20k")
      (footprint "eagle-import:0207_10")
      (libsource (lib "eagle-import") (part "R-US_0207/10"))
    )
    (comp (ref "R161")
      (value "20k")
      (footprint "eagle-import:0207_10")
      (libsource (lib "eagle-import") (part "R-US_0207/10"))
    )
    (comp (ref "R162")
      (value "10k")
      (footprint "eagle-import:0207_10")
      (libsource (lib "eagle-import") (part "R-US_0207/10"))
    )
    (comp (ref "R163")
      (value "40k")
      (footprint "eagle-import:0207_10")
      (libsource (lib "eagle-import") (part "R-US_0207/10"))
    )
    (comp (ref "R164")
      (value "10k")
      (footprint "eagle-import:0207_10")
      (libsource (lib "eagle-import") (part "R-US_0207/10"))
    )
    (comp (ref "R165")
      (value "17k")
      (footprint "eagle-import:0207_10")
      (libsource (lib "eagle-import") (part "R-US_0207/10"))
    )
    (comp (ref "R166")
      (value "13k")
      (footprint "eagle-import:0207_10")
      (libsource (lib "eagle-import") (part "R-US_0207/10"))
    )
    (comp (ref "R167")
      (value "1M")
      (footprint "eagle-import:0207_10")
      (libsource (lib "eagle-import") (part "resistor_R-US_0207/10"))
    )
    (comp (ref "R168")
      (value "1M")
      (footprint "eagle-import:0207_10")
      (libsource (lib "eagle-import") (part "resistor_R-US_0207/10"))
    )
    (comp (ref "R169")
      (value "1M")
      (footprint "eagle-import:0207_10")
      (libsource (lib "eagle-import") (part "resistor_R-US_0207/10"))
    )
    (comp (ref "R170")
      (value "1M")
      (footprint "eagle-import:0207_10")
      (libsource (lib "eagle-import") (part "resistor_R-US_0207/10"))
    )
    (comp (ref "R171")
      (value "1M")
      (footprint "eagle-import:0207_10")
      (libsource (lib "eagle-import") (part "resistor_R-US_0207/10"))
    )
    (comp (ref "R172")
      (value "100k")
      (footprint "eagle-import:0207_10")
      (libsource (lib "eagle-import") (part "R-US_0207/10"))
    )
    (comp (ref "R173")
      (value "10k")
      (footprint "eagle-import:0207_10")
      (libsource (lib "eagle-import") (part "R-US_0207/10"))
    )
    (comp (ref "R174")
      (value "20k")
      (footprint "eagle-import:0207_10")
      (libsource (lib "eagle-import") (part "R-US_0207/10"))
    )
    (comp (ref "R175")
      (value "16k")
      (footprint "eagle-import:0207_10")
      (libsource (lib "eagle-import") (part "R-US_0207/10"))
    )
    (comp (ref "R176")
      (value "12.75k")
      (footprint "eagle-import:0207_10")
      (libsource (lib "eagle-import") (part "R-US_0207/10"))
    )
    (comp (ref "R177")
      (value "10k")
      (footprint "eagle-import:0207_10")
      (libsource (lib "eagle-import") (part "R-US_0207/10"))
    )
    (comp (ref "R179")
      (value "1M")
      (footprint "eagle-import:0207_10")
      (libsource (lib "eagle-import") (part "R-US_0207/10"))
    )
    (comp (ref "R180")
      (value "1M")
      (footprint "eagle-import:0207_10")
      (libsource (lib "eagle-import") (part "R-US_0207/10"))
    )
    (comp (ref "R181")
      (value "1M")
      (footprint "eagle-import:0207_10")
      (libsource (lib "eagle-import") (part "R-US_0207/10"))
    )
    (comp (ref "R182")
      (value "25.5k")
      (footprint "eagle-import:0207_10")
      (libsource (lib "eagle-import") (part "R-US_0207/10"))
    )
    (comp (ref "R183")
      (value "25.5k")
      (footprint "eagle-import:0207_10")
      (libsource (lib "eagle-import") (part "R-US_0207/10"))
    )
    (comp (ref "R184")
      (value "25.5k")
      (footprint "eagle-import:0207_10")
      (libsource (lib "eagle-import") (part "R-US_0207/10"))
    )
    (comp (ref "R185")
      (value "20k")
      (footprint "eagle-import:0207_10")
      (libsource (lib "eagle-import") (part "R-US_0207/10"))
    )
    (comp (ref "R186")
      (value "20k")
      (footprint "eagle-import:0207_10")
      (libsource (lib "eagle-import") (part "R-US_0207/10"))
    )
    (comp (ref "R187")
      (value "10k")
      (footprint "eagle-import:0207_10")
      (libsource (lib "eagle-import") (part "R-US_0207/10"))
    )
    (comp (ref "R188")
      (value "40k")
      (footprint "eagle-import:0207_10")
      (libsource (lib "eagle-import") (part "R-US_0207/10"))
    )
    (comp (ref "R189")
      (value "10k")
      (footprint "eagle-import:0207_10")
      (libsource (lib "eagle-import") (part "R-US_0207/10"))
    )
    (comp (ref "R190")
      (value "17k")
      (footprint "eagle-import:0207_10")
      (libsource (lib "eagle-import") (part "R-US_0207/10"))
    )
    (comp (ref "R191")
      (value "13k")
      (footprint "eagle-import:0207_10")
      (libsource (lib "eagle-import") (part "R-US_0207/10"))
    )
    (comp (ref "R192")
      (value "1M")
      (footprint "eagle-import:0207_10")
      (libsource (lib "eagle-import") (part "resistor_R-US_0207/10"))
    )
    (comp (ref "R193")
      (value "1M")
      (footprint "eagle-import:0207_10")
      (libsource (lib "eagle-import") (part "resistor_R-US_0207/10"))
    )
    (comp (ref "R194")
      (value "1M")
      (footprint "eagle-import:0207_10")
      (libsource (lib "eagle-import") (part "resistor_R-US_0207/10"))
    )
    (comp (ref "R195")
      (value "1M")
      (footprint "eagle-import:0207_10")
      (libsource (lib "eagle-import") (part "resistor_R-US_0207/10"))
    )
    (comp (ref "R196")
      (value "1M")
      (footprint "eagle-import:0207_10")
      (libsource (lib "eagle-import") (part "resistor_R-US_0207/10"))
    )
    (comp (ref "R197")
      (value "100k")
      (footprint "eagle-import:0207_10")
      (libsource (lib "eagle-import") (part "R-US_0207/10"))
    )
    (comp (ref "R198")
      (value "10k")
      (footprint "eagle-import:0207_10")
      (libsource (lib "eagle-import") (part "R-US_0207/10"))
    )
    (comp (ref "R199")
      (value "20k")
      (footprint "eagle-import:0207_10")
      (libsource (lib "eagle-import") (part "R-US_0207/10"))
    )
    (comp (ref "R200")
      (value "16k")
      (footprint "eagle-import:0207_10")
      (libsource (lib "eagle-import") (part "R-US_0207/10"))
    )
    (comp (ref "R201")
      (value "12.75k")
      (footprint "eagle-import:0207_10")
      (libsource (lib "eagle-import") (part "R-US_0207/10"))
    )
    (comp (ref "R202")
      (value "10k")
      (footprint "eagle-import:0207_10")
      (libsource (lib "eagle-import") (part "R-US_0207/10"))
    )
    (comp (ref "R204")
      (value "1M")
      (footprint "eagle-import:0207_10")
      (libsource (lib "eagle-import") (part "R-US_0207/10"))
    )
    (comp (ref "R205")
      (value "1M")
      (footprint "eagle-import:0207_10")
      (libsource (lib "eagle-import") (part "R-US_0207/10"))
    )
    (comp (ref "R206")
      (value "1M")
      (footprint "eagle-import:0207_10")
      (libsource (lib "eagle-import") (part "R-US_0207/10"))
    )
    (comp (ref "R207")
      (value "25.5k")
      (footprint "eagle-import:0207_10")
      (libsource (lib "eagle-import") (part "R-US_0207/10"))
    )
    (comp (ref "R208")
      (value "25.5k")
      (footprint "eagle-import:0207_10")
      (libsource (lib "eagle-import") (part "R-US_0207/10"))
    )
    (comp (ref "R209")
      (value "25.5k")
      (footprint "eagle-import:0207_10")
      (libsource (lib "eagle-import") (part "R-US_0207/10"))
    )
    (comp (ref "T1")
      (value "ZTX560")
      (footprint "eagle-import:TO92")
      (libsource (lib "eagle-import") (part "2N3904"))
    )
    (comp (ref "T2")
      (value "ZTX560")
      (footprint "eagle-import:TO92")
      (libsource (lib "eagle-import") (part "2N3904"))
    )
    (comp (ref "U$1")
      (value "PA97")
      (footprint "eagle-import:7SIP")
      (libsource (lib "eagle-import") (part "PA97"))
    )
    (comp (ref "U$2")
      (value "PA97")
      (footprint "eagle-import:7SIP")
      (libsource (lib "eagle-import") (part "PA97"))
    )
    (comp (ref "U$3")
      (value "PA97")
      (footprint "eagle-import:7SIP")
      (libsource (lib "eagle-import") (part "PA97"))
    )
    (comp (ref "U$4")
      (value "PA97")
      (footprint "eagle-import:7SIP")
      (libsource (lib "eagle-import") (part "PA97"))
    )
    (comp (ref "U$5")
      (value "PA97")
      (footprint "eagle-import:7SIP")
      (libsource (lib "eagle-import") (part "PA97"))
    )
    (comp (ref "U$6")
      (value "PA97")
      (footprint "eagle-import:7SIP")
      (libsource (lib "eagle-import") (part "PA97"))
    )
    (comp (ref "U$7")
      (value "PA97")
      (footprint "eagle-import:7SIP")
      (libsource (lib "eagle-import") (part "PA97"))
    )
    (comp (ref "U$8")
      (value "PA97")
      (footprint "eagle-import:7SIP")
      (libsource (lib "eagle-import") (part "PA97"))
    )
  )
  (nets
    (net (code "1") (name "+5V") (class "Default")
      (node (ref "C6") (pin "1") (pinfunction "1_1") (pintype "passive"))
      (node (ref "DISPLAYPOWERJ25") (pin "P$1") (pinfunction "S_P$1") (pintype "passive"))
      (node (ref "IC10") (pin "5") (pinfunction "VL_5") (pintype "input"))
      (node (ref "IC12") (pin "5") (pinfunction "VL_5") (pintype "input"))
      (node (ref "IC14") (pin "5") (pinfunction "VL_5") (pintype "input"))
      (node (ref "IC16") (pin "5") (pinfunction "VL_5") (pintype "input"))
      (node (ref "IC3") (pin "5") (pinfunction "VL_5") (pintype "input"))
      (node (ref "IC4") (pin "5") (pinfunction "VL_5") (pintype "input"))
      (node (ref "IC6") (pin "5") (pinfunction "VL_5") (pintype "input"))
      (node (ref "IC8") (pin "5") (pinfunction "VL_5") (pintype "input"))
      (node (ref "MAN/EXT") (pin "P$1") (pinfunction "S_P$1") (pintype "passive"))
      (node (ref "POWER") (pin "4") (pinfunction "S_4") (pintype "passive"))
      (node (ref "POWER") (pin "5") (pinfunction "S_5") (pintype "passive"))
      (node (ref "R35") (pin "2") (pinfunction "2_2") (pintype "passive"))
    )
    (net (code "2") (name "+15V") (class "Default")
      (node (ref "C2") (pin "1") (pinfunction "1_1") (pintype "passive"))
      (node (ref "IC1") (pin "8") (pinfunction "V+_8") (pintype "power_in"))
      (node (ref "IC10") (pin "4") (pinfunction "V+_4") (pintype "power_in"))
      (node (ref "IC11") (pin "8") (pinfunction "V+_8") (pintype "power_in"))
      (node (ref "IC12") (pin "4") (pinfunction "V+_4") (pintype "power_in"))
      (node (ref "IC13") (pin "8") (pinfunction "V+_8") (pintype "power_in"))
      (node (ref "IC14") (pin "4") (pinfunction "V+_4") (pintype "power_in"))
      (node (ref "IC15") (pin "8") (pinfunction "V+_8") (pintype "power_in"))
      (node (ref "IC16") (pin "4") (pinfunction "V+_4") (pintype "power_in"))
      (node (ref "IC2") (pin "8") (pinfunction "V+_8") (pintype "power_in"))
      (node (ref "IC3") (pin "4") (pinfunction "V+_4") (pintype "power_in"))
      (node (ref "IC4") (pin "4") (pinfunction "V+_4") (pintype "power_in"))
      (node (ref "IC5") (pin "8") (pinfunction "V+_8") (pintype "power_in"))
      (node (ref "IC6") (pin "4") (pinfunction "V+_4") (pintype "power_in"))
      (node (ref "IC7") (pin "8") (pinfunction "V+_8") (pintype "power_in"))
      (node (ref "IC8") (pin "4") (pinfunction "V+_4") (pintype "power_in"))
      (node (ref "IC9") (pin "8") (pinfunction "V+_8") (pintype "power_in"))
      (node (ref "POWER") (pin "6") (pinfunction "S_6") (pintype "passive"))
      (node (ref "R1") (pin "1") (pinfunction "1_1") (pintype "passive"))
      (node (ref "R101") (pin "2") (pinfunction "2_2") (pintype "passive"))
      (node (ref "R110") (pin "1") (pinfunction "1_1") (pintype "passive"))
      (node (ref "R116") (pin "2") (pinfunction "2_2") (pintype "passive"))
      (node (ref "R126") (pin "2") (pinfunction "2_2") (pintype "passive"))
      (node (ref "R13") (pin "1") (pinfunction "1_1") (pintype "passive"))
      (node (ref "R135") (pin "1") (pinfunction "1_1") (pintype "passive"))
      (node (ref "R141") (pin "2") (pinfunction "2_2") (pintype "passive"))
      (node (ref "R151") (pin "2") (pinfunction "2_2") (pintype "passive"))
      (node (ref "R160") (pin "1") (pinfunction "1_1") (pintype "passive"))
      (node (ref "R166") (pin "2") (pinfunction "2_2") (pintype "passive"))
      (node (ref "R176") (pin "2") (pinfunction "2_2") (pintype "passive"))
      (node (ref "R185") (pin "1") (pinfunction "1_1") (pintype "passive"))
      (node (ref "R191") (pin "2") (pinfunction "2_2") (pintype "passive"))
      (node (ref "R20") (pin "2") (pinfunction "2_2") (pintype "passive"))
      (node (ref "R201") (pin "2") (pinfunction "2_2") (pintype "passive"))
      (node (ref "R30") (pin "2") (pinfunction "2_2") (pintype "passive"))
      (node (ref "R41") (pin "2") (pinfunction "2_2") (pintype "passive"))
      (node (ref "R51") (pin "2") (pinfunction "2_2") (pintype "passive"))
      (node (ref "R60") (pin "1") (pinfunction "1_1") (pintype "passive"))
      (node (ref "R66") (pin "2") (pinfunction "2_2") (pintype "passive"))
      (node (ref "R76") (pin "2") (pinfunction "2_2") (pintype "passive"))
      (node (ref "R85") (pin "1") (pinfunction "1_1") (pintype "passive"))
      (node (ref "R91") (pin "2") (pinfunction "2_2") (pintype "passive"))
    )
    (net (code "3") (name "-15V") (class "Default")
      (node (ref "C1") (pin "1") (pinfunction "1_1") (pintype "passive"))
      (node (ref "IC1") (pin "4") (pinfunction "V-_4") (pintype "power_in"))
      (node (ref "IC10") (pin "7") (pinfunction "V-_7") (pintype "power_in"))
      (node (ref "IC11") (pin "4") (pinfunction "V-_4") (pintype "power_in"))
      (node (ref "IC12") (pin "7") (pinfunction "V-_7") (pintype "power_in"))
      (node (ref "IC13") (pin "4") (pinfunction "V-_4") (pintype "power_in"))
      (node (ref "IC14") (pin "7") (pinfunction "V-_7") (pintype "power_in"))
      (node (ref "IC15") (pin "4") (pinfunction "V-_4") (pintype "power_in"))
      (node (ref "IC16") (pin "7") (pinfunction "V-_7") (pintype "power_in"))
      (node (ref "IC2") (pin "4") (pinfunction "V-_4") (pintype "power_in"))
      (node (ref "IC3") (pin "7") (pinfunction "V-_7") (pintype "power_in"))
      (node (ref "IC4") (pin "7") (pinfunction "V-_7") (pintype "power_in"))
      (node (ref "IC5") (pin "4") (pinfunction "V-_4") (pintype "power_in"))
      (node (ref "IC6") (pin "7") (pinfunction "V-_7") (pintype "power_in"))
      (node (ref "IC7") (pin "4") (pinfunction "V-_4") (pintype "power_in"))
      (node (ref "IC8") (pin "7") (pinfunction "V-_7") (pintype "power_in"))
      (node (ref "IC9") (pin "4") (pinfunction "V-_4") (pintype "power_in"))
      (node (ref "POWER") (pin "1") (pinfunction "S_1") (pintype "passive"))
      (node (ref "R100") (pin "1") (pinfunction "1_1") (pintype "passive"))
      (node (ref "R111") (pin "1") (pinfunction "1_1") (pintype "passive"))
      (node (ref "R115") (pin "1") (pinfunction "1_1") (pintype "passive"))
      (node (ref "R125") (pin "1") (pinfunction "1_1") (pintype "passive"))
      (node (ref "R136") (pin "1") (pinfunction "1_1") (pintype "passive"))
      (node (ref "R14") (pin "1") (pinfunction "1_1") (pintype "passive"))
      (node (ref "R140") (pin "1") (pinfunction "1_1") (pintype "passive"))
      (node (ref "R150") (pin "1") (pinfunction "1_1") (pintype "passive"))
      (node (ref "R161") (pin "1") (pinfunction "1_1") (pintype "passive"))
      (node (ref "R165") (pin "1") (pinfunction "1_1") (pintype "passive"))
      (node (ref "R175") (pin "1") (pinfunction "1_1") (pintype "passive"))
      (node (ref "R186") (pin "1") (pinfunction "1_1") (pintype "passive"))
      (node (ref "R19") (pin "1") (pinfunction "1_1") (pintype "passive"))
      (node (ref "R190") (pin "1") (pinfunction "1_1") (pintype "passive"))
      (node (ref "R200") (pin "1") (pinfunction "1_1") (pintype "passive"))
      (node (ref "R29") (pin "1") (pinfunction "1_1") (pintype "passive"))
      (node (ref "R36") (pin "1") (pinfunction "1_1") (pintype "passive"))
      (node (ref "R40") (pin "1") (pinfunction "1_1") (pintype "passive"))
      (node (ref "R50") (pin "1") (pinfunction "1_1") (pintype "passive"))
      (node (ref "R61") (pin "1") (pinfunction "1_1") (pintype "passive"))
      (node (ref "R65") (pin "1") (pinfunction "1_1") (pintype "passive"))
      (node (ref "R75") (pin "1") (pinfunction "1_1") (pintype "passive"))
      (node (ref "R86") (pin "1") (pinfunction "1_1") (pintype "passive"))
      (node (ref "R90") (pin "1") (pinfunction "1_1") (pintype "passive"))
    )
    (net (code "4") (name "/MAN") (class "Default")
      (node (ref "IC10") (pin "6") (pinfunction "IN_6") (pintype "input"))
      (node (ref "IC12") (pin "6") (pinfunction "IN_6") (pintype "input"))
      (node (ref "IC14") (pin "6") (pinfunction "IN_6") (pintype "input"))
      (node (ref "IC16") (pin "6") (pinfunction "IN_6") (pintype "input"))
      (node (ref "IC3") (pin "6") (pinfunction "IN_6") (pintype "input"))
      (node (ref "IC4") (pin "6") (pinfunction "IN_6") (pintype "input"))
      (node (ref "IC6") (pin "6") (pinfunction "IN_6") (pintype "input"))
      (node (ref "IC8") (pin "6") (pinfunction "IN_6") (pintype "input"))
      (node (ref "MAN/EXT") (pin "P$2") (pinfunction "S_P$2") (pintype "passive"))
      (node (ref "R32") (pin "2") (pinfunction "2_2") (pintype "passive"))
    )
    (net (code "5") (name "/V+_SAFE") (class "Default")
      (node (ref "Q1") (pin "1") (pinfunction "C_1") (pintype "passive"))
      (node (ref "U$1") (pin "P$7") (pinfunction "V+_P$7") (pintype "power_in"))
      (node (ref "U$2") (pin "P$7") (pinfunction "V+_P$7") (pintype "power_in"))
      (node (ref "U$3") (pin "P$7") (pinfunction "V+_P$7") (pintype "power_in"))
      (node (ref "U$4") (pin "P$7") (pinfunction "V+_P$7") (pintype "power_in"))
      (node (ref "U$5") (pin "P$7") (pinfunction "V+_P$7") (pintype "power_in"))
      (node (ref "U$6") (pin "P$7") (pinfunction "V+_P$7") (pintype "power_in"))
      (node (ref "U$7") (pin "P$7") (pinfunction "V+_P$7") (pintype "power_in"))
      (node (ref "U$8") (pin "P$7") (pinfunction "V+_P$7") (pintype "power_in"))
    )
    (net (code "6") (name "/V-_SAFE") (class "Default")
      (node (ref "T2") (pin "1") (pinfunction "C_1") (pintype "passive"))
      (node (ref "U$1") (pin "P$6") (pinfunction "V-_P$6") (pintype "power_in"))
      (node (ref "U$2") (pin "P$6") (pinfunction "V-_P$6") (pintype "power_in"))
      (node (ref "U$3") (pin "P$6") (pinfunction "V-_P$6") (pintype "power_in"))
      (node (ref "U$4") (pin "P$6") (pinfunction "V-_P$6") (pintype "power_in"))
      (node (ref "U$5") (pin "P$6") (pinfunction "V-_P$6") (pintype "power_in"))
      (node (ref "U$6") (pin "P$6") (pinfunction "V-_P$6") (pintype "power_in"))
      (node (ref "U$7") (pin "P$6") (pinfunction "V-_P$6") (pintype "power_in"))
      (node (ref "U$8") (pin "P$6") (pinfunction "V-_P$6") (pintype "power_in"))
    )
    (net (code "7") (name "/VIN+") (class "Default")
      (node (ref "D13") (pin "A") (pinfunction "A_A") (pintype "passive"))
      (node (ref "D17") (pin "A") (pinfunction "A_A") (pintype "passive"))
      (node (ref "D21") (pin "A") (pinfunction "A_A") (pintype "passive"))
      (node (ref "D25") (pin "A") (pinfunction "A_A") (pintype "passive"))
      (node (ref "D29") (pin "A") (pinfunction "A_A") (pintype "passive"))
      (node (ref "D33") (pin "A") (pinfunction "A_A") (pintype "passive"))
      (node (ref "D5") (pin "A") (pinfunction "A_A") (pintype "passive"))
      (node (ref "D9") (pin "A") (pinfunction "A_A") (pintype "passive"))
      (node (ref "IC10") (pin "1") (pinfunction "D_1") (pintype "bidirectional"))
      (node (ref "IC12") (pin "1") (pinfunction "D_1") (pintype "bidirectional"))
      (node (ref "IC14") (pin "1") (pinfunction "D_1") (pintype "bidirectional"))
      (node (ref "IC16") (pin "1") (pinfunction "D_1") (pintype "bidirectional"))
      (node (ref "IC3") (pin "1") (pinfunction "D_1") (pintype "bidirectional"))
      (node (ref "IC4") (pin "1") (pinfunction "D_1") (pintype "bidirectional"))
      (node (ref "IC6") (pin "1") (pinfunction "D_1") (pintype "bidirectional"))
      (node (ref "IC8") (pin "1") (pinfunction "D_1") (pintype "bidirectional"))
      (node (ref "U$1") (pin "P$2") (pinfunction "+IN_P$2") (pintype "input"))
      (node (ref "U$2") (pin "P$2") (pinfunction "+IN_P$2") (pintype "input"))
      (node (ref "U$3") (pin "P$2") (pinfunction "+IN_P$2") (pintype "input"))
      (node (ref "U$4") (pin "P$2") (pinfunction "+IN_P$2") (pintype "input"))
      (node (ref "U$5") (pin "P$2") (pinfunction "+IN_P$2") (pintype "input"))
      (node (ref "U$6") (pin "P$2") (pinfunction "+IN_P$2") (pintype "input"))
      (node (ref "U$7") (pin "P$2") (pinfunction "+IN_P$2") (pintype "input"))
      (node (ref "U$8") (pin "P$2") (pinfunction "+IN_P$2") (pintype "input"))
    )
    (net (code "8") (name "/VIN-") (class "Default")
      (node (ref "C11") (pin "1") (pinfunction "1_1") (pintype "passive"))
      (node (ref "C13") (pin "1") (pinfunction "1_1") (pintype "passive"))
      (node (ref "C15") (pin "1") (pinfunction "1_1") (pintype "passive"))
      (node (ref "C17") (pin "1") (pinfunction "1_1") (pintype "passive"))
      (node (ref "C19") (pin "1") (pinfunction "1_1") (pintype "passive"))
      (node (ref "C21") (pin "1") (pinfunction "1_1") (pintype "passive"))
      (node (ref "C23") (pin "1") (pinfunction "1_1") (pintype "passive"))
      (node (ref "C7") (pin "1") (pinfunction "1_1") (pintype "passive"))
      (node (ref "D10") (pin "A") (pinfunction "A_A") (pintype "passive"))
      (node (ref "D14") (pin "A") (pinfunction "A_A") (pintype "passive"))
      (node (ref "D18") (pin "A") (pinfunction "A_A") (pintype "passive"))
      (node (ref "D22") (pin "A") (pinfunction "A_A") (pintype "passive"))
      (node (ref "D26") (pin "A") (pinfunction "A_A") (pintype "passive"))
      (node (ref "D30") (pin "A") (pinfunction "A_A") (pintype "passive"))
      (node (ref "D34") (pin "A") (pinfunction "A_A") (pintype "passive"))
      (node (ref "D6") (pin "A") (pinfunction "A_A") (pintype "passive"))
      (node (ref "R104") (pin "1") (pinfunction "1_1") (pintype "passive"))
      (node (ref "R107") (pin "2") (pinfunction "2_2") (pintype "passive"))
      (node (ref "R129") (pin "1") (pinfunction "1_1") (pintype "passive"))
      (node (ref "R132") (pin "2") (pinfunction "2_2") (pintype "passive"))
      (node (ref "R154") (pin "1") (pinfunction "1_1") (pintype "passive"))
      (node (ref "R157") (pin "2") (pinfunction "2_2") (pintype "passive"))
      (node (ref "R179") (pin "1") (pinfunction "1_1") (pintype "passive"))
      (node (ref "R182") (pin "2") (pinfunction "2_2") (pintype "passive"))
      (node (ref "R204") (pin "1") (pinfunction "1_1") (pintype "passive"))
      (node (ref "R207") (pin "2") (pinfunction "2_2") (pintype "passive"))
      (node (ref "R4") (pin "1") (pinfunction "1_1") (pintype "passive"))
      (node (ref "R5") (pin "2") (pinfunction "2_2") (pintype "passive"))
      (node (ref "R54") (pin "1") (pinfunction "1_1") (pintype "passive"))
      (node (ref "R57") (pin "2") (pinfunction "2_2") (pintype "passive"))
      (node (ref "R79") (pin "1") (pinfunction "1_1") (pintype "passive"))
      (node (ref "R82") (pin "2") (pinfunction "2_2") (pintype "passive"))
      (node (ref "U$1") (pin "P$1") (pinfunction "-IN_P$1") (pintype "input"))
      (node (ref "U$2") (pin "P$1") (pinfunction "-IN_P$1") (pintype "input"))
      (node (ref "U$3") (pin "P$1") (pinfunction "-IN_P$1") (pintype "input"))
      (node (ref "U$4") (pin "P$1") (pinfunction "-IN_P$1") (pintype "input"))
      (node (ref "U$5") (pin "P$1") (pinfunction "-IN_P$1") (pintype "input"))
      (node (ref "U$6") (pin "P$1") (pinfunction "-IN_P$1") (pintype "input"))
      (node (ref "U$7") (pin "P$1") (pinfunction "-IN_P$1") (pintype "input"))
      (node (ref "U$8") (pin "P$1") (pinfunction "-IN_P$1") (pintype "input"))
    )
    (net (code "9") (name "GND") (class "Default")
      (node (ref "C1") (pin "2") (pinfunction "2_2") (pintype "passive"))
      (node (ref "C2") (pin "2") (pinfunction "2_2") (pintype "passive"))
      (node (ref "C3") (pin "2") (pinfunction "2_2") (pintype "passive"))
      (node (ref "C4") (pin "2") (pinfunction "2_2") (pintype "passive"))
      (node (ref "C6") (pin "2") (pinfunction "2_2") (pintype "passive"))
      (node (ref "D1") (pin "A") (pinfunction "A_A") (pintype "passive"))
      (node (ref "D11") (pin "A") (pinfunction "A_A") (pintype "passive"))
      (node (ref "D15") (pin "A") (pinfunction "A_A") (pintype "passive"))
      (node (ref "D19") (pin "A") (pinfunction "A_A") (pintype "passive"))
      (node (ref "D2") (pin "A") (pinfunction "A_A") (pintype "passive"))
      (node (ref "D23") (pin "A") (pinfunction "A_A") (pintype "passive"))
      (node (ref "D27") (pin "A") (pinfunction "A_A") (pintype "passive"))
      (node (ref "D3") (pin "C") (pinfunction "C_C") (pintype "passive"))
      (node (ref "D31") (pin "A") (pinfunction "A_A") (pintype "passive"))
      (node (ref "D7") (pin "A") (pinfunction "A_A") (pintype "passive"))
      (node (ref "DISPLAY1") (pin "P$2") (pinfunction "S_P$2") (pintype "passive"))
      (node (ref "DISPLAYPOWERJ25") (pin "P$2") (pinfunction "S_P$2") (pintype "passive"))
      (node (ref "EXTERNAL") (pin "10") (pinfunction "F_10") (pintype "passive"))
      (node (ref "EXTERNAL") (pin "12") (pinfunction "F_12") (pintype "passive"))
      (node (ref "EXTERNAL") (pin "14") (pinfunction "F_14") (pintype "passive"))
      (node (ref "EXTERNAL") (pin "16") (pinfunction "F_16") (pintype "passive"))
      (node (ref "EXTERNAL") (pin "2") (pinfunction "F_2") (pintype "passive"))
      (node (ref "EXTERNAL") (pin "25") (pinfunction "F_25") (pintype "passive"))
      (node (ref "EXTERNAL") (pin "4") (pinfunction "F_4") (pintype "passive"))
      (node (ref "EXTERNAL") (pin "6") (pinfunction "F_6") (pintype "passive"))
      (node (ref "EXTERNAL") (pin "8") (pinfunction "F_8") (pintype "passive"))
      (node (ref "HVIN") (pin "P$1") (pinfunction "S_P$1") (pintype "passive"))
      (node (ref "HVIN") (pin "P$2") (pinfunction "S_P$2") (pintype "passive"))
      (node (ref "IC10") (pin "3") (pinfunction "GND_3") (pintype "power_in"))
      (node (ref "IC12") (pin "3") (pinfunction "GND_3") (pintype "power_in"))
      (node (ref "IC14") (pin "3") (pinfunction "GND_3") (pintype "power_in"))
      (node (ref "IC16") (pin "3") (pinfunction "GND_3") (pintype "power_in"))
      (node (ref "IC3") (pin "3") (pinfunction "GND_3") (pintype "power_in"))
      (node (ref "IC4") (pin "3") (pinfunction "GND_3") (pintype "power_in"))
      (node (ref "IC6") (pin "3") (pinfunction "GND_3") (pintype "power_in"))
      (node (ref "IC8") (pin "3") (pinfunction "GND_3") (pintype "power_in"))
      (node (ref "J26") (pin "P$2") (pinfunction "S_P$2") (pintype "passive"))
      (node (ref "POWER") (pin "2") (pinfunction "S_2") (pintype "passive"))
      (node (ref "POWER") (pin "3") (pinfunction "S_3") (pintype "passive"))
      (node (ref "R109") (pin "2") (pinfunction "2_2") (pintype "passive"))
      (node (ref "R122") (pin "1") (pinfunction "1_1") (pintype "passive"))
      (node (ref "R134") (pin "2") (pinfunction "2_2") (pintype "passive"))
      (node (ref "R147") (pin "1") (pinfunction "1_1") (pintype "passive"))
      (node (ref "R15") (pin "2") (pinfunction "2_2") (pintype "passive"))
      (node (ref "R159") (pin "2") (pinfunction "2_2") (pintype "passive"))
      (node (ref "R172") (pin "1") (pinfunction "1_1") (pintype "passive"))
      (node (ref "R184") (pin "2") (pinfunction "2_2") (pintype "passive"))
      (node (ref "R197") (pin "1") (pinfunction "1_1") (pintype "passive"))
      (node (ref "R209") (pin "2") (pinfunction "2_2") (pintype "passive"))
      (node (ref "R26") (pin "1") (pinfunction "1_1") (pintype "passive"))
      (node (ref "R32") (pin "1") (pinfunction "1_1") (pintype "passive"))
      (node (ref "R34") (pin "2") (pinfunction "2_2") (pintype "passive"))
      (node (ref "R47") (pin "1") (pinfunction "1_1") (pintype "passive"))
      (node (ref "R59") (pin "2") (pinfunction "2_2") (pintype "passive"))
      (node (ref "R7") (pin "2") (pinfunction "2_2") (pintype "passive"))
      (node (ref "R72") (pin "1") (pinfunction "1_1") (pintype "passive"))
      (node (ref "R84") (pin "2") (pinfunction "2_2") (pintype "passive"))
      (node (ref "R9") (pin "1") (pinfunction "1_1") (pintype "passive"))
      (node (ref "R97") (pin "1") (pinfunction "1_1") (pintype "passive"))
    )
    (net (code "10") (name "Net-(D1-PadC)") (class "Default")
      (node (ref "D1") (pin "C") (pinfunction "C_C") (pintype "passive"))
      (node (ref "D4") (pin "C") (pinfunction "C_C") (pintype "passive"))
    )
    (net (code "11") (name "Net-(D5-PadC)") (class "Default")
      (node (ref "D5") (pin "C") (pinfunction "C_C") (pintype "passive"))
      (node (ref "D6") (pin "C") (pinfunction "C_C") (pintype "passive"))
    )
    (net (code "12") (name "Net-(D7-PadC)") (class "Default")
      (node (ref "D7") (pin "C") (pinfunction "C_C") (pintype "passive"))
      (node (ref "D8") (pin "C") (pinfunction "C_C") (pintype "passive"))
    )
    (net (code "13") (name "Net-(D10-PadC)") (class "Default")
      (node (ref "D10") (pin "C") (pinfunction "C_C") (pintype "passive"))
      (node (ref "D9") (pin "C") (pinfunction "C_C") (pintype "passive"))
    )
    (net (code "14") (name "Net-(D11-PadC)") (class "Default")
      (node (ref "D11") (pin "C") (pinfunction "C_C") (pintype "passive"))
      (node (ref "D12") (pin "C") (pinfunction "C_C") (pintype "passive"))
    )
    (net (code "15") (name "Net-(D13-PadC)") (class "Default")
      (node (ref "D13") (pin "C") (pinfunction "C_C") (pintype "passive"))
      (node (ref "D14") (pin "C") (pinfunction "C_C") (pintype "passive"))
    )
    (net (code "16") (name "Net-(D15-PadC)") (class "Default")
      (node (ref "D15") (pin "C") (pinfunction "C_C") (pintype "passive"))
      (node (ref "D16") (pin "C") (pinfunction "C_C") (pintype "passive"))
    )
    (net (code "17") (name "Net-(D17-PadC)") (class "Default")
      (node (ref "D17") (pin "C") (pinfunction "C_C") (pintype "passive"))
      (node (ref "D18") (pin "C") (pinfunction "C_C") (pintype "passive"))
    )
    (net (code "18") (name "Net-(D19-PadC)") (class "Default")
      (node (ref "D19") (pin "C") (pinfunction "C_C") (pintype "passive"))
      (node (ref "D20") (pin "C") (pinfunction "C_C") (pintype "passive"))
    )
    (net (code "19") (name "Net-(D21-PadC)") (class "Default")
      (node (ref "D21") (pin "C") (pinfunction "C_C") (pintype "passive"))
      (node (ref "D22") (pin "C") (pinfunction "C_C") (pintype "passive"))
    )
    (net (code "20") (name "Net-(D23-PadC)") (class "Default")
      (node (ref "D23") (pin "C") (pinfunction "C_C") (pintype "passive"))
      (node (ref "D24") (pin "C") (pinfunction "C_C") (pintype "passive"))
    )
    (net (code "21") (name "Net-(D25-PadC)") (class "Default")
      (node (ref "D25") (pin "C") (pinfunction "C_C") (pintype "passive"))
      (node (ref "D26") (pin "C") (pinfunction "C_C") (pintype "passive"))
    )
    (net (code "22") (name "Net-(D27-PadC)") (class "Default")
      (node (ref "D27") (pin "C") (pinfunction "C_C") (pintype "passive"))
      (node (ref "D28") (pin "C") (pinfunction "C_C") (pintype "passive"))
    )
    (net (code "23") (name "Net-(D29-PadC)") (class "Default")
      (node (ref "D29") (pin "C") (pinfunction "C_C") (pintype "passive"))
      (node (ref "D30") (pin "C") (pinfunction "C_C") (pintype "passive"))
    )
    (net (code "24") (name "Net-(D31-PadC)") (class "Default")
      (node (ref "D31") (pin "C") (pinfunction "C_C") (pintype "passive"))
      (node (ref "D32") (pin "C") (pinfunction "C_C") (pintype "passive"))
    )
    (net (code "25") (name "Net-(D33-PadC)") (class "Default")
      (node (ref "D33") (pin "C") (pinfunction "C_C") (pintype "passive"))
      (node (ref "D34") (pin "C") (pinfunction "C_C") (pintype "passive"))
    )
    (net (code "26") (name "Net-(DISPLAY1A-S)") (class "Default")
      (node (ref "DISPLAY1") (pin "P$1") (pinfunction "S_P$1") (pintype "passive"))
      (node (ref "R33") (pin "2") (pinfunction "2_2") (pintype "passive"))
      (node (ref "R34") (pin "1") (pinfunction "1_1") (pintype "passive"))
    )
    (net (code "27") (name "Net-(DISPLAYA-S)") (class "Default")
      (node (ref "DISPLAY") (pin "P$1") (pinfunction "S_P$1") (pintype "passive"))
      (node (ref "R25") (pin "1") (pinfunction "1_1") (pintype "passive"))
      (node (ref "R26") (pin "2") (pinfunction "2_2") (pintype "passive"))
      (node (ref "R28") (pin "2") (pinfunction "2_2") (pintype "passive"))
    )
    (net (code "28") (name "Net-(DISPLAYB-S)") (class "Default")
      (node (ref "DISPLAY") (pin "P$2") (pinfunction "S_P$2") (pintype "passive"))
      (node (ref "R46") (pin "1") (pinfunction "1_1") (pintype "passive"))
      (node (ref "R47") (pin "2") (pinfunction "2_2") (pintype "passive"))
      (node (ref "R49") (pin "2") (pinfunction "2_2") (pintype "passive"))
    )
    (net (code "29") (name "Net-(DISPLAYC-S)") (class "Default")
      (node (ref "DISPLAY") (pin "P$3") (pinfunction "S_P$3") (pintype "passive"))
      (node (ref "R71") (pin "1") (pinfunction "1_1") (pintype "passive"))
      (node (ref "R72") (pin "2") (pinfunction "2_2") (pintype "passive"))
      (node (ref "R74") (pin "2") (pinfunction "2_2") (pintype "passive"))
    )
    (net (code "30") (name "Net-(DISPLAYD-S)") (class "Default")
      (node (ref "DISPLAY") (pin "P$4") (pinfunction "S_P$4") (pintype "passive"))
      (node (ref "R96") (pin "1") (pinfunction "1_1") (pintype "passive"))
      (node (ref "R97") (pin "2") (pinfunction "2_2") (pintype "passive"))
      (node (ref "R99") (pin "2") (pinfunction "2_2") (pintype "passive"))
    )
    (net (code "31") (name "Net-(DISPLAYE-S)") (class "Default")
      (node (ref "DISPLAY") (pin "P$5") (pinfunction "S_P$5") (pintype "passive"))
      (node (ref "R121") (pin "1") (pinfunction "1_1") (pintype "passive"))
      (node (ref "R122") (pin "2") (pinfunction "2_2") (pintype "passive"))
      (node (ref "R124") (pin "2") (pinfunction "2_2") (pintype "passive"))
    )
    (net (code "32") (name "Net-(DISPLAYF-S)") (class "Default")
      (node (ref "DISPLAY") (pin "P$6") (pinfunction "S_P$6") (pintype "passive"))
      (node (ref "R146") (pin "1") (pinfunction "1_1") (pintype "passive"))
      (node (ref "R147") (pin "2") (pinfunction "2_2") (pintype "passive"))
      (node (ref "R149") (pin "2") (pinfunction "2_2") (pintype "passive"))
    )
    (net (code "33") (name "Net-(DISPLAYG-S)") (class "Default")
      (node (ref "DISPLAY") (pin "P$7") (pinfunction "S_P$7") (pintype "passive"))
      (node (ref "R171") (pin "1") (pinfunction "1_1") (pintype "passive"))
      (node (ref "R172") (pin "2") (pinfunction "2_2") (pintype "passive"))
      (node (ref "R174") (pin "2") (pinfunction "2_2") (pintype "passive"))
    )
    (net (code "34") (name "Net-(DISPLAYH-S)") (class "Default")
      (node (ref "DISPLAY") (pin "P$8") (pinfunction "S_P$8") (pintype "passive"))
      (node (ref "R196") (pin "1") (pinfunction "1_1") (pintype "passive"))
      (node (ref "R197") (pin "2") (pinfunction "2_2") (pintype "passive"))
      (node (ref "R199") (pin "2") (pinfunction "2_2") (pintype "passive"))
    )
    (net (code "35") (name "Net-(EXTERNALA-F)") (class "Default")
      (node (ref "EXTERNAL") (pin "1") (pinfunction "F_1") (pintype "passive"))
      (node (ref "R16") (pin "2") (pinfunction "2_2") (pintype "passive"))
    )
    (net (code "36") (name "Net-(EXTERNALC-F)") (class "Default")
      (node (ref "EXTERNAL") (pin "11") (pinfunction "F_11") (pintype "passive"))
      (node (ref "R137") (pin "2") (pinfunction "2_2") (pintype "passive"))
    )
    (net (code "37") (name "Net-(EXTERNALE-F)") (class "Default")
      (node (ref "EXTERNAL") (pin "13") (pinfunction "F_13") (pintype "passive"))
      (node (ref "R162") (pin "2") (pinfunction "2_2") (pintype "passive"))
    )
    (net (code "38") (name "Net-(EXTERNALG-F)") (class "Default")
      (node (ref "EXTERNAL") (pin "15") (pinfunction "F_15") (pintype "passive"))
      (node (ref "R187") (pin "2") (pinfunction "2_2") (pintype "passive"))
    )
    (net (code "39") (name "Net-(EXTERNALI-F)") (class "Default")
      (node (ref "EXTERNAL") (pin "17") (pinfunction "F_17") (pintype "passive"))
      (node (ref "IC2") (pin "7") (pinfunction "OUT_7") (pintype "output"))
      (node (ref "R27") (pin "1") (pinfunction "1_1") (pintype "passive"))
    )
    (net (code "40") (name "Net-(EXTERNALJ-F)") (class "Default")
      (node (ref "EXTERNAL") (pin "18") (pinfunction "F_18") (pintype "passive"))
      (node (ref "IC1") (pin "7") (pinfunction "OUT_7") (pintype "output"))
      (node (ref "R48") (pin "1") (pinfunction "1_1") (pintype "passive"))
    )
    (net (code "41") (name "Net-(EXTERNALK-F)") (class "Default")
      (node (ref "EXTERNAL") (pin "19") (pinfunction "F_19") (pintype "passive"))
      (node (ref "IC5") (pin "7") (pinfunction "OUT_7") (pintype "output"))
      (node (ref "R73") (pin "1") (pinfunction "1_1") (pintype "passive"))
    )
    (net (code "42") (name "Net-(EXTERNALM-F)") (class "Default")
      (node (ref "EXTERNAL") (pin "20") (pinfunction "F_20") (pintype "passive"))
      (node (ref "IC7") (pin "7") (pinfunction "OUT_7") (pintype "output"))
      (node (ref "R98") (pin "1") (pinfunction "1_1") (pintype "passive"))
    )
    (net (code "43") (name "Net-(EXTERNALN-F)") (class "Default")
      (node (ref "EXTERNAL") (pin "21") (pinfunction "F_21") (pintype "passive"))
      (node (ref "IC9") (pin "7") (pinfunction "OUT_7") (pintype "output"))
      (node (ref "R123") (pin "1") (pinfunction "1_1") (pintype "passive"))
    )
    (net (code "44") (name "Net-(EXTERNALO-F)") (class "Default")
      (node (ref "EXTERNAL") (pin "22") (pinfunction "F_22") (pintype "passive"))
      (node (ref "IC11") (pin "7") (pinfunction "OUT_7") (pintype "output"))
      (node (ref "R148") (pin "1") (pinfunction "1_1") (pintype "passive"))
    )
    (net (code "45") (name "Net-(EXTERNALP-F)") (class "Default")
      (node (ref "EXTERNAL") (pin "23") (pinfunction "F_23") (pintype "passive"))
      (node (ref "IC13") (pin "7") (pinfunction "OUT_7") (pintype "output"))
      (node (ref "R173") (pin "1") (pinfunction "1_1") (pintype "passive"))
    )
    (net (code "46") (name "Net-(EXTERNALQ-F)") (class "Default")
      (node (ref "EXTERNAL") (pin "24") (pinfunction "F_24") (pintype "passive"))
      (node (ref "IC15") (pin "7") (pinfunction "OUT_7") (pintype "output"))
      (node (ref "R198") (pin "1") (pinfunction "1_1") (pintype "passive"))
    )
    (net (code "47") (name "Net-(EXTERNALS-F)") (class "Default")
      (node (ref "EXTERNAL") (pin "3") (pinfunction "F_3") (pintype "passive"))
      (node (ref "R37") (pin "2") (pinfunction "2_2") (pintype "passive"))
    )
    (net (code "48") (name "Net-(EXTERNALU-F)") (class "Default")
      (node (ref "EXTERNAL") (pin "5") (pinfunction "F_5") (pintype "passive"))
      (node (ref "R62") (pin "2") (pinfunction "2_2") (pintype "passive"))
    )
    (net (code "49") (name "Net-(EXTERNALW-F)") (class "Default")
      (node (ref "EXTERNAL") (pin "7") (pinfunction "F_7") (pintype "passive"))
      (node (ref "R87") (pin "2") (pinfunction "2_2") (pintype "passive"))
    )
    (net (code "50") (name "Net-(EXTERNALY-F)") (class "Default")
      (node (ref "EXTERNAL") (pin "9") (pinfunction "F_9") (pintype "passive"))
      (node (ref "R112") (pin "2") (pinfunction "2_2") (pintype "passive"))
    )
    (net (code "51") (name "Net-(IC1A-+IN)") (class "Default")
      (node (ref "IC1") (pin "3") (pinfunction "+IN_3") (pintype "input"))
      (node (ref "R39") (pin "1") (pinfunction "1_1") (pintype "passive"))
    )
    (net (code "52") (name "Net-(IC1A--IN)") (class "Default")
      (node (ref "IC1") (pin "2") (pinfunction "-IN_2") (pintype "input"))
      (node (ref "R37") (pin "1") (pinfunction "1_1") (pintype "passive"))
      (node (ref "R38") (pin "2") (pinfunction "2_2") (pintype "passive"))
    )
    (net (code "53") (name "Net-(IC1A-OUT)") (class "Default")
      (node (ref "IC1") (pin "1") (pinfunction "OUT_1") (pintype "output"))
      (node (ref "IC4") (pin "8") (pinfunction "S2_8") (pintype "bidirectional"))
      (node (ref "R38") (pin "1") (pinfunction "1_1") (pintype "passive"))
    )
    (net (code "54") (name "Net-(IC1B-+IN)") (class "Default")
      (node (ref "IC1") (pin "5") (pinfunction "+IN_5") (pintype "input"))
      (node (ref "R48") (pin "2") (pinfunction "2_2") (pintype "passive"))
      (node (ref "R49") (pin "1") (pinfunction "1_1") (pintype "passive"))
    )
    (net (code "55") (name "Net-(IC1B--IN)") (class "Default")
      (node (ref "IC1") (pin "6") (pinfunction "-IN_6") (pintype "input"))
      (node (ref "R52") (pin "1") (pinfunction "1_1") (pintype "passive"))
    )
    (net (code "56") (name "Net-(IC2A-+IN)") (class "Default")
      (node (ref "IC2") (pin "3") (pinfunction "+IN_3") (pintype "input"))
      (node (ref "R18") (pin "1") (pinfunction "1_1") (pintype "passive"))
    )
    (net (code "57") (name "Net-(IC2A--IN)") (class "Default")
      (node (ref "IC2") (pin "2") (pinfunction "-IN_2") (pintype "input"))
      (node (ref "R16") (pin "1") (pinfunction "1_1") (pintype "passive"))
      (node (ref "R17") (pin "2") (pinfunction "2_2") (pintype "passive"))
    )
    (net (code "58") (name "Net-(IC2A-OUT)") (class "Default")
      (node (ref "IC2") (pin "1") (pinfunction "OUT_1") (pintype "output"))
      (node (ref "IC3") (pin "8") (pinfunction "S2_8") (pintype "bidirectional"))
      (node (ref "R17") (pin "1") (pinfunction "1_1") (pintype "passive"))
    )
    (net (code "59") (name "Net-(IC2B-+IN)") (class "Default")
      (node (ref "IC2") (pin "5") (pinfunction "+IN_5") (pintype "input"))
      (node (ref "R27") (pin "2") (pinfunction "2_2") (pintype "passive"))
      (node (ref "R28") (pin "1") (pinfunction "1_1") (pintype "passive"))
    )
    (net (code "60") (name "Net-(IC2B--IN)") (class "Default")
      (node (ref "IC2") (pin "6") (pinfunction "-IN_6") (pintype "input"))
      (node (ref "R31") (pin "1") (pinfunction "1_1") (pintype "passive"))
    )
    (net (code "61") (name "Net-(IC3A-S1)") (class "Default")
      (node (ref "IC3") (pin "2") (pinfunction "S1_2") (pintype "bidirectional"))
      (node (ref "POT1") (pin "P$4") (pinfunction "S_P$4") (pintype "passive"))
    )
    (net (code "62") (name "Net-(IC4A-S1)") (class "Default")
      (node (ref "IC4") (pin "2") (pinfunction "S1_2") (pintype "bidirectional"))
      (node (ref "POT2") (pin "P$4") (pinfunction "S_P$4") (pintype "passive"))
    )
    (net (code "63") (name "Net-(IC5A-+IN)") (class "Default")
      (node (ref "IC5") (pin "3") (pinfunction "+IN_3") (pintype "input"))
      (node (ref "R64") (pin "1") (pinfunction "1_1") (pintype "passive"))
    )
    (net (code "64") (name "Net-(IC5A--IN)") (class "Default")
      (node (ref "IC5") (pin "2") (pinfunction "-IN_2") (pintype "input"))
      (node (ref "R62") (pin "1") (pinfunction "1_1") (pintype "passive"))
      (node (ref "R63") (pin "2") (pinfunction "2_2") (pintype "passive"))
    )
    (net (code "65") (name "Net-(IC5A-OUT)") (class "Default")
      (node (ref "IC5") (pin "1") (pinfunction "OUT_1") (pintype "output"))
      (node (ref "IC6") (pin "8") (pinfunction "S2_8") (pintype "bidirectional"))
      (node (ref "R63") (pin "1") (pinfunction "1_1") (pintype "passive"))
    )
    (net (code "66") (name "Net-(IC5B-+IN)") (class "Default")
      (node (ref "IC5") (pin "5") (pinfunction "+IN_5") (pintype "input"))
      (node (ref "R73") (pin "2") (pinfunction "2_2") (pintype "passive"))
      (node (ref "R74") (pin "1") (pinfunction "1_1") (pintype "passive"))
    )
    (net (code "67") (name "Net-(IC5B--IN)") (class "Default")
      (node (ref "IC5") (pin "6") (pinfunction "-IN_6") (pintype "input"))
      (node (ref "R77") (pin "1") (pinfunction "1_1") (pintype "passive"))
    )
    (net (code "68") (name "Net-(IC6A-S1)") (class "Default")
      (node (ref "IC6") (pin "2") (pinfunction "S1_2") (pintype "bidirectional"))
      (node (ref "POT3") (pin "P$4") (pinfunction "S_P$4") (pintype "passive"))
    )
    (net (code "69") (name "Net-(IC7A-+IN)") (class "Default")
      (node (ref "IC7") (pin "3") (pinfunction "+IN_3") (pintype "input"))
      (node (ref "R89") (pin "1") (pinfunction "1_1") (pintype "passive"))
    )
    (net (code "70") (name "Net-(IC7A--IN)") (class "Default")
      (node (ref "IC7") (pin "2") (pinfunction "-IN_2") (pintype "input"))
      (node (ref "R87") (pin "1") (pinfunction "1_1") (pintype "passive"))
      (node (ref "R88") (pin "2") (pinfunction "2_2") (pintype "passive"))
    )
    (net (code "71") (name "Net-(IC7A-OUT)") (class "Default")
      (node (ref "IC7") (pin "1") (pinfunction "OUT_1") (pintype "output"))
      (node (ref "IC8") (pin "8") (pinfunction "S2_8") (pintype "bidirectional"))
      (node (ref "R88") (pin "1") (pinfunction "1_1") (pintype "passive"))
    )
    (net (code "72") (name "Net-(IC7B-+IN)") (class "Default")
      (node (ref "IC7") (pin "5") (pinfunction "+IN_5") (pintype "input"))
      (node (ref "R98") (pin "2") (pinfunction "2_2") (pintype "passive"))
      (node (ref "R99") (pin "1") (pinfunction "1_1") (pintype "passive"))
    )
    (net (code "73") (name "Net-(IC7B--IN)") (class "Default")
      (node (ref "IC7") (pin "6") (pinfunction "-IN_6") (pintype "input"))
      (node (ref "R102") (pin "1") (pinfunction "1_1") (pintype "passive"))
    )
    (net (code "74") (name "Net-(IC8A-S1)") (class "Default")
      (node (ref "IC8") (pin "2") (pinfunction "S1_2") (pintype "bidirectional"))
      (node (ref "POT4") (pin "P$4") (pinfunction "S_P$4") (pintype "passive"))
    )
    (net (code "75") (name "Net-(IC9A-+IN)") (class "Default")
      (node (ref "IC9") (pin "3") (pinfunction "+IN_3") (pintype "input"))
      (node (ref "R114") (pin "1") (pinfunction "1_1") (pintype "passive"))
    )
    (net (code "76") (name "Net-(IC9A--IN)") (class "Default")
      (node (ref "IC9") (pin "2") (pinfunction "-IN_2") (pintype "input"))
      (node (ref "R112") (pin "1") (pinfunction "1_1") (pintype "passive"))
      (node (ref "R113") (pin "2") (pinfunction "2_2") (pintype "passive"))
    )
    (net (code "77") (name "Net-(IC9B-+IN)") (class "Default")
      (node (ref "IC9") (pin "5") (pinfunction "+IN_5") (pintype "input"))
      (node (ref "R123") (pin "2") (pinfunction "2_2") (pintype "passive"))
      (node (ref "R124") (pin "1") (pinfunction "1_1") (pintype "passive"))
    )
    (net (code "78") (name "Net-(IC9B--IN)") (class "Default")
      (node (ref "IC9") (pin "6") (pinfunction "-IN_6") (pintype "input"))
      (node (ref "R127") (pin "1") (pinfunction "1_1") (pintype "passive"))
    )
    (net (code "79") (name "Net-(IC10A-S1)") (class "Default")
      (node (ref "IC10") (pin "2") (pinfunction "S1_2") (pintype "bidirectional"))
      (node (ref "POT5") (pin "P$4") (pinfunction "S_P$4") (pintype "passive"))
    )
    (net (code "80") (name "Net-(IC10A-S2)") (class "Default")
      (node (ref "IC10") (pin "8") (pinfunction "S2_8") (pintype "bidirectional"))
      (node (ref "IC9") (pin "1") (pinfunction "OUT_1") (pintype "output"))
      (node (ref "R113") (pin "1") (pinfunction "1_1") (pintype "passive"))
    )
    (net (code "81") (name "Net-(IC11A-+IN)") (class "Default")
      (node (ref "IC11") (pin "3") (pinfunction "+IN_3") (pintype "input"))
      (node (ref "R139") (pin "1") (pinfunction "1_1") (pintype "passive"))
    )
    (net (code "82") (name "Net-(IC11A--IN)") (class "Default")
      (node (ref "IC11") (pin "2") (pinfunction "-IN_2") (pintype "input"))
      (node (ref "R137") (pin "1") (pinfunction "1_1") (pintype "passive"))
      (node (ref "R138") (pin "2") (pinfunction "2_2") (pintype "passive"))
    )
    (net (code "83") (name "Net-(IC11A-OUT)") (class "Default")
      (node (ref "IC11") (pin "1") (pinfunction "OUT_1") (pintype "output"))
      (node (ref "IC12") (pin "8") (pinfunction "S2_8") (pintype "bidirectional"))
      (node (ref "R138") (pin "1") (pinfunction "1_1") (pintype "passive"))
    )
    (net (code "84") (name "Net-(IC11B-+IN)") (class "Default")
      (node (ref "IC11") (pin "5") (pinfunction "+IN_5") (pintype "input"))
      (node (ref "R148") (pin "2") (pinfunction "2_2") (pintype "passive"))
      (node (ref "R149") (pin "1") (pinfunction "1_1") (pintype "passive"))
    )
    (net (code "85") (name "Net-(IC11B--IN)") (class "Default")
      (node (ref "IC11") (pin "6") (pinfunction "-IN_6") (pintype "input"))
      (node (ref "R152") (pin "1") (pinfunction "1_1") (pintype "passive"))
    )
    (net (code "86") (name "Net-(IC12A-S1)") (class "Default")
      (node (ref "IC12") (pin "2") (pinfunction "S1_2") (pintype "bidirectional"))
      (node (ref "POT6") (pin "P$4") (pinfunction "S_P$4") (pintype "passive"))
    )
    (net (code "87") (name "Net-(IC13A-+IN)") (class "Default")
      (node (ref "IC13") (pin "3") (pinfunction "+IN_3") (pintype "input"))
      (node (ref "R164") (pin "1") (pinfunction "1_1") (pintype "passive"))
    )
    (net (code "88") (name "Net-(IC13A--IN)") (class "Default")
      (node (ref "IC13") (pin "2") (pinfunction "-IN_2") (pintype "input"))
      (node (ref "R162") (pin "1") (pinfunction "1_1") (pintype "passive"))
      (node (ref "R163") (pin "2") (pinfunction "2_2") (pintype "passive"))
    )
    (net (code "89") (name "Net-(IC13A-OUT)") (class "Default")
      (node (ref "IC13") (pin "1") (pinfunction "OUT_1") (pintype "output"))
      (node (ref "IC14") (pin "8") (pinfunction "S2_8") (pintype "bidirectional"))
      (node (ref "R163") (pin "1") (pinfunction "1_1") (pintype "passive"))
    )
    (net (code "90") (name "Net-(IC13B-+IN)") (class "Default")
      (node (ref "IC13") (pin "5") (pinfunction "+IN_5") (pintype "input"))
      (node (ref "R173") (pin "2") (pinfunction "2_2") (pintype "passive"))
      (node (ref "R174") (pin "1") (pinfunction "1_1") (pintype "passive"))
    )
    (net (code "91") (name "Net-(IC13B--IN)") (class "Default")
      (node (ref "IC13") (pin "6") (pinfunction "-IN_6") (pintype "input"))
      (node (ref "R177") (pin "1") (pinfunction "1_1") (pintype "passive"))
    )
    (net (code "92") (name "Net-(IC14A-S1)") (class "Default")
      (node (ref "IC14") (pin "2") (pinfunction "S1_2") (pintype "bidirectional"))
      (node (ref "POT7") (pin "P$4") (pinfunction "S_P$4") (pintype "passive"))
    )
    (net (code "93") (name "Net-(IC15A-+IN)") (class "Default")
      (node (ref "IC15") (pin "3") (pinfunction "+IN_3") (pintype "input"))
      (node (ref "R189") (pin "1") (pinfunction "1_1") (pintype "passive"))
    )
    (net (code "94") (name "Net-(IC15A--IN)") (class "Default")
      (node (ref "IC15") (pin "2") (pinfunction "-IN_2") (pintype "input"))
      (node (ref "R187") (pin "1") (pinfunction "1_1") (pintype "passive"))
      (node (ref "R188") (pin "2") (pinfunction "2_2") (pintype "passive"))
    )
    (net (code "95") (name "Net-(IC15A-OUT)") (class "Default")
      (node (ref "IC15") (pin "1") (pinfunction "OUT_1") (pintype "output"))
      (node (ref "IC16") (pin "8") (pinfunction "S2_8") (pintype "bidirectional"))
      (node (ref "R188") (pin "1") (pinfunction "1_1") (pintype "passive"))
    )
    (net (code "96") (name "Net-(IC15B-+IN)") (class "Default")
      (node (ref "IC15") (pin "5") (pinfunction "+IN_5") (pintype "input"))
      (node (ref "R198") (pin "2") (pinfunction "2_2") (pintype "passive"))
      (node (ref "R199") (pin "1") (pinfunction "1_1") (pintype "passive"))
    )
    (net (code "97") (name "Net-(IC15B--IN)") (class "Default")
      (node (ref "IC15") (pin "6") (pinfunction "-IN_6") (pintype "input"))
      (node (ref "R202") (pin "1") (pinfunction "1_1") (pintype "passive"))
    )
    (net (code "98") (name "Net-(IC16A-S1)") (class "Default")
      (node (ref "IC16") (pin "2") (pinfunction "S1_2") (pintype "bidirectional"))
      (node (ref "POT8") (pin "P$4") (pinfunction "S_P$4") (pintype "passive"))
    )
    (net (code "99") (name "Net-(J23A-S)") (class "Default")
      (node (ref "J23") (pin "P$1") (pinfunction "S_P$1") (pintype "passive"))
      (node (ref "R33") (pin "1") (pinfunction "1_1") (pintype "passive"))
    )
    (net (code "100") (name "Net-(J26A-S)") (class "Default")
      (node (ref "J26") (pin "P$1") (pinfunction "S_P$1") (pintype "passive"))
      (node (ref "R35") (pin "1") (pinfunction "1_1") (pintype "passive"))
    )
    (net (code "101") (name "Net-(OUTB-P$1)") (class "Default")
      (node (ref "C11") (pin "2") (pinfunction "2_2") (pintype "passive"))
      (node (ref "D4") (pin "A") (pinfunction "A_A") (pintype "passive"))
      (node (ref "OUT") (pin "P$2") (pinfunction "P$1_P$2") (pintype "bidirectional"))
      (node (ref "R42") (pin "2") (pinfunction "2_2") (pintype "passive"))
      (node (ref "R56") (pin "2") (pinfunction "2_2") (pintype "passive"))
      (node (ref "U$1") (pin "P$5") (pinfunction "OUT_P$5") (pintype "output"))
    )
    (net (code "102") (name "Net-(OUTC-P$1)") (class "Default")
      (node (ref "C13") (pin "2") (pinfunction "2_2") (pintype "passive"))
      (node (ref "D12") (pin "A") (pinfunction "A_A") (pintype "passive"))
      (node (ref "OUT") (pin "P$3") (pinfunction "P$1_P$3") (pintype "bidirectional"))
      (node (ref "R67") (pin "2") (pinfunction "2_2") (pintype "passive"))
      (node (ref "R81") (pin "2") (pinfunction "2_2") (pintype "passive"))
      (node (ref "U$2") (pin "P$5") (pinfunction "OUT_P$5") (pintype "output"))
    )
    (net (code "103") (name "Net-(OUTD-P$1)") (class "Default")
      (node (ref "C15") (pin "2") (pinfunction "2_2") (pintype "passive"))
      (node (ref "D16") (pin "A") (pinfunction "A_A") (pintype "passive"))
      (node (ref "OUT") (pin "P$4") (pinfunction "P$1_P$4") (pintype "bidirectional"))
      (node (ref "R106") (pin "2") (pinfunction "2_2") (pintype "passive"))
      (node (ref "R92") (pin "2") (pinfunction "2_2") (pintype "passive"))
      (node (ref "U$3") (pin "P$5") (pinfunction "OUT_P$5") (pintype "output"))
    )
    (net (code "104") (name "Net-(OUTE-P$1)") (class "Default")
      (node (ref "C17") (pin "2") (pinfunction "2_2") (pintype "passive"))
      (node (ref "D20") (pin "A") (pinfunction "A_A") (pintype "passive"))
      (node (ref "OUT") (pin "P$5") (pinfunction "P$1_P$5") (pintype "bidirectional"))
      (node (ref "R117") (pin "2") (pinfunction "2_2") (pintype "passive"))
      (node (ref "R131") (pin "2") (pinfunction "2_2") (pintype "passive"))
      (node (ref "U$5") (pin "P$5") (pinfunction "OUT_P$5") (pintype "output"))
    )
    (net (code "105") (name "Net-(OUTF-P$1)") (class "Default")
      (node (ref "C19") (pin "2") (pinfunction "2_2") (pintype "passive"))
      (node (ref "D24") (pin "A") (pinfunction "A_A") (pintype "passive"))
      (node (ref "OUT") (pin "P$6") (pinfunction "P$1_P$6") (pintype "bidirectional"))
      (node (ref "R142") (pin "2") (pinfunction "2_2") (pintype "passive"))
      (node (ref "R156") (pin "2") (pinfunction "2_2") (pintype "passive"))
      (node (ref "U$6") (pin "P$5") (pinfunction "OUT_P$5") (pintype "output"))
    )
    (net (code "106") (name "Net-(OUTG-P$1)") (class "Default")
      (node (ref "C21") (pin "2") (pinfunction "2_2") (pintype "passive"))
      (node (ref "D28") (pin "A") (pinfunction "A_A") (pintype "passive"))
      (node (ref "OUT") (pin "P$7") (pinfunction "P$1_P$7") (pintype "bidirectional"))
      (node (ref "R167") (pin "2") (pinfunction "2_2") (pintype "passive"))
      (node (ref "R181") (pin "2") (pinfunction "2_2") (pintype "passive"))
      (node (ref "U$7") (pin "P$5") (pinfunction "OUT_P$5") (pintype "output"))
    )
    (net (code "107") (name "Net-(OUTH-P$1)") (class "Default")
      (node (ref "C23") (pin "2") (pinfunction "2_2") (pintype "passive"))
      (node (ref "D32") (pin "A") (pinfunction "A_A") (pintype "passive"))
      (node (ref "OUT") (pin "P$8") (pinfunction "P$1_P$8") (pintype "bidirectional"))
      (node (ref "R192") (pin "2") (pinfunction "2_2") (pintype "passive"))
      (node (ref "R206") (pin "2") (pinfunction "2_2") (pintype "passive"))
      (node (ref "U$8") (pin "P$5") (pinfunction "OUT_P$5") (pintype "output"))
    )
    (net (code "108") (name "Net-(POT1A-S)") (class "Default")
      (node (ref "POT1") (pin "P$1") (pinfunction "S_P$1") (pintype "passive"))
      (node (ref "R14") (pin "2") (pinfunction "2_2") (pintype "passive"))
    )
    (net (code "109") (name "Net-(POT1B-S)") (class "Default")
      (node (ref "POT1") (pin "P$2") (pinfunction "S_P$2") (pintype "passive"))
      (node (ref "R13") (pin "2") (pinfunction "2_2") (pintype "passive"))
    )
    (net (code "110") (name "Net-(POT2A-S)") (class "Default")
      (node (ref "POT2") (pin "P$1") (pinfunction "S_P$1") (pintype "passive"))
      (node (ref "R36") (pin "2") (pinfunction "2_2") (pintype "passive"))
    )
    (net (code "111") (name "Net-(POT2B-S)") (class "Default")
      (node (ref "POT2") (pin "P$2") (pinfunction "S_P$2") (pintype "passive"))
      (node (ref "R1") (pin "2") (pinfunction "2_2") (pintype "passive"))
    )
    (net (code "112") (name "Net-(POT3A-S)") (class "Default")
      (node (ref "POT3") (pin "P$1") (pinfunction "S_P$1") (pintype "passive"))
      (node (ref "R61") (pin "2") (pinfunction "2_2") (pintype "passive"))
    )
    (net (code "113") (name "Net-(POT3B-S)") (class "Default")
      (node (ref "POT3") (pin "P$2") (pinfunction "S_P$2") (pintype "passive"))
      (node (ref "R60") (pin "2") (pinfunction "2_2") (pintype "passive"))
    )
    (net (code "114") (name "Net-(POT4A-S)") (class "Default")
      (node (ref "POT4") (pin "P$1") (pinfunction "S_P$1") (pintype "passive"))
      (node (ref "R86") (pin "2") (pinfunction "2_2") (pintype "passive"))
    )
    (net (code "115") (name "Net-(POT4B-S)") (class "Default")
      (node (ref "POT4") (pin "P$2") (pinfunction "S_P$2") (pintype "passive"))
      (node (ref "R85") (pin "2") (pinfunction "2_2") (pintype "passive"))
    )
    (net (code "116") (name "Net-(POT5A-S)") (class "Default")
      (node (ref "POT5") (pin "P$1") (pinfunction "S_P$1") (pintype "passive"))
      (node (ref "R111") (pin "2") (pinfunction "2_2") (pintype "passive"))
    )
    (net (code "117") (name "Net-(POT5B-S)") (class "Default")
      (node (ref "POT5") (pin "P$2") (pinfunction "S_P$2") (pintype "passive"))
      (node (ref "R110") (pin "2") (pinfunction "2_2") (pintype "passive"))
    )
    (net (code "118") (name "Net-(POT6A-S)") (class "Default")
      (node (ref "POT6") (pin "P$1") (pinfunction "S_P$1") (pintype "passive"))
      (node (ref "R136") (pin "2") (pinfunction "2_2") (pintype "passive"))
    )
    (net (code "119") (name "Net-(POT6B-S)") (class "Default")
      (node (ref "POT6") (pin "P$2") (pinfunction "S_P$2") (pintype "passive"))
      (node (ref "R135") (pin "2") (pinfunction "2_2") (pintype "passive"))
    )
    (net (code "120") (name "Net-(POT7A-S)") (class "Default")
      (node (ref "POT7") (pin "P$1") (pinfunction "S_P$1") (pintype "passive"))
      (node (ref "R161") (pin "2") (pinfunction "2_2") (pintype "passive"))
    )
    (net (code "121") (name "Net-(POT7B-S)") (class "Default")
      (node (ref "POT7") (pin "P$2") (pinfunction "S_P$2") (pintype "passive"))
      (node (ref "R160") (pin "2") (pinfunction "2_2") (pintype "passive"))
    )
    (net (code "122") (name "Net-(POT8A-S)") (class "Default")
      (node (ref "POT8") (pin "P$1") (pinfunction "S_P$1") (pintype "passive"))
      (node (ref "R186") (pin "2") (pinfunction "2_2") (pintype "passive"))
    )
    (net (code "123") (name "Net-(POT8B-S)") (class "Default")
      (node (ref "POT8") (pin "P$2") (pinfunction "S_P$2") (pintype "passive"))
      (node (ref "R185") (pin "2") (pinfunction "2_2") (pintype "passive"))
    )
    (net (code "124") (name "Net-(Q1-B)") (class "Default")
      (node (ref "C8") (pin "2") (pinfunction "2_2") (pintype "passive"))
      (node (ref "Q1") (pin "2") (pinfunction "B_2") (pintype "passive"))
      (node (ref "Q2") (pin "1") (pinfunction "C_1") (pintype "passive"))
      (node (ref "R9") (pin "2") (pinfunction "2_2") (pintype "passive"))
    )
    (net (code "125") (name "Net-(Q1-E)") (class "Default")
      (node (ref "Q1") (pin "3") (pinfunction "E_3") (pintype "passive"))
      (node (ref "R10") (pin "2") (pinfunction "2_2") (pintype "passive"))
      (node (ref "R8") (pin "1") (pinfunction "1_1") (pintype "passive"))
    )
    (net (code "126") (name "Net-(Q2-B)") (class "Default")
      (node (ref "C8") (pin "1") (pinfunction "1_1") (pintype "passive"))
      (node (ref "Q2") (pin "2") (pinfunction "B_2") (pintype "passive"))
      (node (ref "R10") (pin "1") (pinfunction "1_1") (pintype "passive"))
    )
    (net (code "127") (name "Net-(R2-Pad1)") (class "Default")
      (node (ref "R2") (pin "1") (pinfunction "1_1") (pintype "passive"))
      (node (ref "R4") (pin "2") (pinfunction "2_2") (pintype "passive"))
    )
    (net (code "128") (name "Net-(R2-Pad2)") (class "Default")
      (node (ref "R2") (pin "2") (pinfunction "2_2") (pintype "passive"))
      (node (ref "R3") (pin "1") (pinfunction "1_1") (pintype "passive"))
    )
    (net (code "129") (name "Net-(R5-Pad1)") (class "Default")
      (node (ref "R5") (pin "1") (pinfunction "1_1") (pintype "passive"))
      (node (ref "R6") (pin "2") (pinfunction "2_2") (pintype "passive"))
    )
    (net (code "130") (name "Net-(R6-Pad1)") (class "Default")
      (node (ref "R6") (pin "1") (pinfunction "1_1") (pintype "passive"))
      (node (ref "R7") (pin "1") (pinfunction "1_1") (pintype "passive"))
    )
    (net (code "131") (name "Net-(R18-Pad2)") (class "Default")
      (node (ref "R18") (pin "2") (pinfunction "2_2") (pintype "passive"))
      (node (ref "R19") (pin "2") (pinfunction "2_2") (pintype "passive"))
      (node (ref "R20") (pin "1") (pinfunction "1_1") (pintype "passive"))
    )
    (net (code "132") (name "Net-(R21-Pad1)") (class "Default")
      (node (ref "R21") (pin "1") (pinfunction "1_1") (pintype "passive"))
      (node (ref "R22") (pin "2") (pinfunction "2_2") (pintype "passive"))
    )
    (net (code "133") (name "Net-(R22-Pad1)") (class "Default")
      (node (ref "R22") (pin "1") (pinfunction "1_1") (pintype "passive"))
      (node (ref "R23") (pin "2") (pinfunction "2_2") (pintype "passive"))
    )
    (net (code "134") (name "Net-(R23-Pad1)") (class "Default")
      (node (ref "R23") (pin "1") (pinfunction "1_1") (pintype "passive"))
      (node (ref "R24") (pin "2") (pinfunction "2_2") (pintype "passive"))
    )
    (net (code "135") (name "Net-(R24-Pad1)") (class "Default")
      (node (ref "R24") (pin "1") (pinfunction "1_1") (pintype "passive"))
      (node (ref "R25") (pin "2") (pinfunction "2_2") (pintype "passive"))
    )
    (net (code "136") (name "Net-(R29-Pad2)") (class "Default")
      (node (ref "R29") (pin "2") (pinfunction "2_2") (pintype "passive"))
      (node (ref "R30") (pin "1") (pinfunction "1_1") (pintype "passive"))
      (node (ref "R31") (pin "2") (pinfunction "2_2") (pintype "passive"))
    )
    (net (code "137") (name "Net-(R39-Pad2)") (class "Default")
      (node (ref "R39") (pin "2") (pinfunction "2_2") (pintype "passive"))
      (node (ref "R40") (pin "2") (pinfunction "2_2") (pintype "passive"))
      (node (ref "R41") (pin "1") (pinfunction "1_1") (pintype "passive"))
    )
    (net (code "138") (name "Net-(R42-Pad1)") (class "Default")
      (node (ref "R42") (pin "1") (pinfunction "1_1") (pintype "passive"))
      (node (ref "R43") (pin "2") (pinfunction "2_2") (pintype "passive"))
    )
    (net (code "139") (name "Net-(R43-Pad1)") (class "Default")
      (node (ref "R43") (pin "1") (pinfunction "1_1") (pintype "passive"))
      (node (ref "R44") (pin "2") (pinfunction "2_2") (pintype "passive"))
    )
    (net (code "140") (name "Net-(R44-Pad1)") (class "Default")
      (node (ref "R44") (pin "1") (pinfunction "1_1") (pintype "passive"))
      (node (ref "R45") (pin "2") (pinfunction "2_2") (pintype "passive"))
    )
    (net (code "141") (name "Net-(R45-Pad1)") (class "Default")
      (node (ref "R45") (pin "1") (pinfunction "1_1") (pintype "passive"))
      (node (ref "R46") (pin "2") (pinfunction "2_2") (pintype "passive"))
    )
    (net (code "142") (name "Net-(R50-Pad2)") (class "Default")
      (node (ref "R50") (pin "2") (pinfunction "2_2") (pintype "passive"))
      (node (ref "R51") (pin "1") (pinfunction "1_1") (pintype "passive"))
      (node (ref "R52") (pin "2") (pinfunction "2_2") (pintype "passive"))
    )
    (net (code "143") (name "Net-(R54-Pad2)") (class "Default")
      (node (ref "R54") (pin "2") (pinfunction "2_2") (pintype "passive"))
      (node (ref "R55") (pin "1") (pinfunction "1_1") (pintype "passive"))
    )
    (net (code "144") (name "Net-(R55-Pad2)") (class "Default")
      (node (ref "R55") (pin "2") (pinfunction "2_2") (pintype "passive"))
      (node (ref "R56") (pin "1") (pinfunction "1_1") (pintype "passive"))
    )
    (net (code "145") (name "Net-(R57-Pad1)") (class "Default")
      (node (ref "R57") (pin "1") (pinfunction "1_1") (pintype "passive"))
      (node (ref "R58") (pin "2") (pinfunction "2_2") (pintype "passive"))
    )
    (net (code "146") (name "Net-(R58-Pad1)") (class "Default")
      (node (ref "R58") (pin "1") (pinfunction "1_1") (pintype "passive"))
      (node (ref "R59") (pin "1") (pinfunction "1_1") (pintype "passive"))
    )
    (net (code "147") (name "Net-(R64-Pad2)") (class "Default")
      (node (ref "R64") (pin "2") (pinfunction "2_2") (pintype "passive"))
      (node (ref "R65") (pin "2") (pinfunction "2_2") (pintype "passive"))
      (node (ref "R66") (pin "1") (pinfunction "1_1") (pintype "passive"))
    )
    (net (code "148") (name "Net-(R67-Pad1)") (class "Default")
      (node (ref "R67") (pin "1") (pinfunction "1_1") (pintype "passive"))
      (node (ref "R68") (pin "2") (pinfunction "2_2") (pintype "passive"))
    )
    (net (code "149") (name "Net-(R68-Pad1)") (class "Default")
      (node (ref "R68") (pin "1") (pinfunction "1_1") (pintype "passive"))
      (node (ref "R69") (pin "2") (pinfunction "2_2") (pintype "passive"))
    )
    (net (code "150") (name "Net-(R69-Pad1)") (class "Default")
      (node (ref "R69") (pin "1") (pinfunction "1_1") (pintype "passive"))
      (node (ref "R70") (pin "2") (pinfunction "2_2") (pintype "passive"))
    )
    (net (code "151") (name "Net-(R70-Pad1)") (class "Default")
      (node (ref "R70") (pin "1") (pinfunction "1_1") (pintype "passive"))
      (node (ref "R71") (pin "2") (pinfunction "2_2") (pintype "passive"))
    )
    (net (code "152") (name "Net-(R75-Pad2)") (class "Default")
      (node (ref "R75") (pin "2") (pinfunction "2_2") (pintype "passive"))
      (node (ref "R76") (pin "1") (pinfunction "1_1") (pintype "passive"))
      (node (ref "R77") (pin "2") (pinfunction "2_2") (pintype "passive"))
    )
    (net (code "153") (name "Net-(R79-Pad2)") (class "Default")
      (node (ref "R79") (pin "2") (pinfunction "2_2") (pintype "passive"))
      (node (ref "R80") (pin "1") (pinfunction "1_1") (pintype "passive"))
    )
    (net (code "154") (name "Net-(R80-Pad2)") (class "Default")
      (node (ref "R80") (pin "2") (pinfunction "2_2") (pintype "passive"))
      (node (ref "R81") (pin "1") (pinfunction "1_1") (pintype "passive"))
    )
    (net (code "155") (name "Net-(R82-Pad1)") (class "Default")
      (node (ref "R82") (pin "1") (pinfunction "1_1") (pintype "passive"))
      (node (ref "R83") (pin "2") (pinfunction "2_2") (pintype "passive"))
    )
    (net (code "156") (name "Net-(R83-Pad1)") (class "Default")
      (node (ref "R83") (pin "1") (pinfunction "1_1") (pintype "passive"))
      (node (ref "R84") (pin "1") (pinfunction "1_1") (pintype "passive"))
    )
    (net (code "157") (name "Net-(R89-Pad2)") (class "Default")
      (node (ref "R89") (pin "2") (pinfunction "2_2") (pintype "passive"))
      (node (ref "R90") (pin "2") (pinfunction "2_2") (pintype "passive"))
      (node (ref "R91") (pin "1") (pinfunction "1_1") (pintype "passive"))
    )
    (net (code "158") (name "Net-(R92-Pad1)") (class "Default")
      (node (ref "R92") (pin "1") (pinfunction "1_1") (pintype "passive"))
      (node (ref "R93") (pin "2") (pinfunction "2_2") (pintype "passive"))
    )
    (net (code "159") (name "Net-(R93-Pad1)") (class "Default")
      (node (ref "R93") (pin "1") (pinfunction "1_1") (pintype "passive"))
      (node (ref "R94") (pin "2") (pinfunction "2_2") (pintype "passive"))
    )
    (net (code "160") (name "Net-(R94-Pad1)") (class "Default")
      (node (ref "R94") (pin "1") (pinfunction "1_1") (pintype "passive"))
      (node (ref "R95") (pin "2") (pinfunction "2_2") (pintype "passive"))
    )
    (net (code "161") (name "Net-(R95-Pad1)") (class "Default")
      (node (ref "R95") (pin "1") (pinfunction "1_1") (pintype "passive"))
      (node (ref "R96") (pin "2") (pinfunction "2_2") (pintype "passive"))
    )
    (net (code "162") (name "Net-(R100-Pad2)") (class "Default")
      (node (ref "R100") (pin "2") (pinfunction "2_2") (pintype "passive"))
      (node (ref "R101") (pin "1") (pinfunction "1_1") (pintype "passive"))
      (node (ref "R102") (pin "2") (pinfunction "2_2") (pintype "passive"))
    )
    (net (code "163") (name "Net-(R104-Pad2)") (class "Default")
      (node (ref "R104") (pin "2") (pinfunction "2_2") (pintype "passive"))
      (node (ref "R105") (pin "1") (pinfunction "1_1") (pintype "passive"))
    )
    (net (code "164") (name "Net-(R105-Pad2)") (class "Default")
      (node (ref "R105") (pin "2") (pinfunction "2_2") (pintype "passive"))
      (node (ref "R106") (pin "1") (pinfunction "1_1") (pintype "passive"))
    )
    (net (code "165") (name "Net-(R107-Pad1)") (class "Default")
      (node (ref "R107") (pin "1") (pinfunction "1_1") (pintype "passive"))
      (node (ref "R108") (pin "2") (pinfunction "2_2") (pintype "passive"))
    )
    (net (code "166") (name "Net-(R108-Pad1)") (class "Default")
      (node (ref "R108") (pin "1") (pinfunction "1_1") (pintype "passive"))
      (node (ref "R109") (pin "1") (pinfunction "1_1") (pintype "passive"))
    )
    (net (code "167") (name "Net-(R114-Pad2)") (class "Default")
      (node (ref "R114") (pin "2") (pinfunction "2_2") (pintype "passive"))
      (node (ref "R115") (pin "2") (pinfunction "2_2") (pintype "passive"))
      (node (ref "R116") (pin "1") (pinfunction "1_1") (pintype "passive"))
    )
    (net (code "168") (name "Net-(R117-Pad1)") (class "Default")
      (node (ref "R117") (pin "1") (pinfunction "1_1") (pintype "passive"))
      (node (ref "R118") (pin "2") (pinfunction "2_2") (pintype "passive"))
    )
    (net (code "169") (name "Net-(R118-Pad1)") (class "Default")
      (node (ref "R118") (pin "1") (pinfunction "1_1") (pintype "passive"))
      (node (ref "R119") (pin "2") (pinfunction "2_2") (pintype "passive"))
    )
    (net (code "170") (name "Net-(R119-Pad1)") (class "Default")
      (node (ref "R119") (pin "1") (pinfunction "1_1") (pintype "passive"))
      (node (ref "R120") (pin "2") (pinfunction "2_2") (pintype "passive"))
    )
    (net (code "171") (name "Net-(R120-Pad1)") (class "Default")
      (node (ref "R120") (pin "1") (pinfunction "1_1") (pintype "passive"))
      (node (ref "R121") (pin "2") (pinfunction "2_2") (pintype "passive"))
    )
    (net (code "172") (name "Net-(R125-Pad2)") (class "Default")
      (node (ref "R125") (pin "2") (pinfunction "2_2") (pintype "passive"))
      (node (ref "R126") (pin "1") (pinfunction "1_1") (pintype "passive"))
      (node (ref "R127") (pin "2") (pinfunction "2_2") (pintype "passive"))
    )
    (net (code "173") (name "Net-(R129-Pad2)") (class "Default")
      (node (ref "R129") (pin "2") (pinfunction "2_2") (pintype "passive"))
      (node (ref "R130") (pin "1") (pinfunction "1_1") (pintype "passive"))
    )
    (net (code "174") (name "Net-(R130-Pad2)") (class "Default")
      (node (ref "R130") (pin "2") (pinfunction "2_2") (pintype "passive"))
      (node (ref "R131") (pin "1") (pinfunction "1_1") (pintype "passive"))
    )
    (net (code "175") (name "Net-(R132-Pad1)") (class "Default")
      (node (ref "R132") (pin "1") (pinfunction "1_1") (pintype "passive"))
      (node (ref "R133") (pin "2") (pinfunction "2_2") (pintype "passive"))
    )
    (net (code "176") (name "Net-(R133-Pad1)") (class "Default")
      (node (ref "R133") (pin "1") (pinfunction "1_1") (pintype "passive"))
      (node (ref "R134") (pin "1") (pinfunction "1_1") (pintype "passive"))
    )
    (net (code "177") (name "Net-(R139-Pad2)") (class "Default")
      (node (ref "R139") (pin "2") (pinfunction "2_2") (pintype "passive"))
      (node (ref "R140") (pin "2") (pinfunction "2_2") (pintype "passive"))
      (node (ref "R141") (pin "1") (pinfunction "1_1") (pintype "passive"))
    )
    (net (code "178") (name "Net-(R142-Pad1)") (class "Default")
      (node (ref "R142") (pin "1") (pinfunction "1_1") (pintype "passive"))
      (node (ref "R143") (pin "2") (pinfunction "2_2") (pintype "passive"))
    )
    (net (code "179") (name "Net-(R143-Pad1)") (class "Default")
      (node (ref "R143") (pin "1") (pinfunction "1_1") (pintype "passive"))
      (node (ref "R144") (pin "2") (pinfunction "2_2") (pintype "passive"))
    )
    (net (code "180") (name "Net-(R144-Pad1)") (class "Default")
      (node (ref "R144") (pin "1") (pinfunction "1_1") (pintype "passive"))
      (node (ref "R145") (pin "2") (pinfunction "2_2") (pintype "passive"))
    )
    (net (code "181") (name "Net-(R145-Pad1)") (class "Default")
      (node (ref "R145") (pin "1") (pinfunction "1_1") (pintype "passive"))
      (node (ref "R146") (pin "2") (pinfunction "2_2") (pintype "passive"))
    )
    (net (code "182") (name "Net-(R150-Pad2)") (class "Default")
      (node (ref "R150") (pin "2") (pinfunction "2_2") (pintype "passive"))
      (node (ref "R151") (pin "1") (pinfunction "1_1") (pintype "passive"))
      (node (ref "R152") (pin "2") (pinfunction "2_2") (pintype "passive"))
    )
    (net (code "183") (name "Net-(R154-Pad2)") (class "Default")
      (node (ref "R154") (pin "2") (pinfunction "2_2") (pintype "passive"))
      (node (ref "R155") (pin "1") (pinfunction "1_1") (pintype "passive"))
    )
    (net (code "184") (name "Net-(R155-Pad2)") (class "Default")
      (node (ref "R155") (pin "2") (pinfunction "2_2") (pintype "passive"))
      (node (ref "R156") (pin "1") (pinfunction "1_1") (pintype "passive"))
    )
    (net (code "185") (name "Net-(R157-Pad1)") (class "Default")
      (node (ref "R157") (pin "1") (pinfunction "1_1") (pintype "passive"))
      (node (ref "R158") (pin "2") (pinfunction "2_2") (pintype "passive"))
    )
    (net (code "186") (name "Net-(R158-Pad1)") (class "Default")
      (node (ref "R158") (pin "1") (pinfunction "1_1") (pintype "passive"))
      (node (ref "R159") (pin "1") (pinfunction "1_1") (pintype "passive"))
    )
    (net (code "187") (name "Net-(R164-Pad2)") (class "Default")
      (node (ref "R164") (pin "2") (pinfunction "2_2") (pintype "passive"))
      (node (ref "R165") (pin "2") (pinfunction "2_2") (pintype "passive"))
      (node (ref "R166") (pin "1") (pinfunction "1_1") (pintype "passive"))
    )
    (net (code "188") (name "Net-(R167-Pad1)") (class "Default")
      (node (ref "R167") (pin "1") (pinfunction "1_1") (pintype "passive"))
      (node (ref "R168") (pin "2") (pinfunction "2_2") (pintype "passive"))
    )
    (net (code "189") (name "Net-(R168-Pad1)") (class "Default")
      (node (ref "R168") (pin "1") (pinfunction "1_1") (pintype "passive"))
      (node (ref "R169") (pin "2") (pinfunction "2_2") (pintype "passive"))
    )
    (net (code "190") (name "Net-(R169-Pad1)") (class "Default")
      (node (ref "R169") (pin "1") (pinfunction "1_1") (pintype "passive"))
      (node (ref "R170") (pin "2") (pinfunction "2_2") (pintype "passive"))
    )
    (net (code "191") (name "Net-(R170-Pad1)") (class "Default")
      (node (ref "R170") (pin "1") (pinfunction "1_1") (pintype "passive"))
      (node (ref "R171") (pin "2") (pinfunction "2_2") (pintype "passive"))
    )
    (net (code "192") (name "Net-(R175-Pad2)") (class "Default")
      (node (ref "R175") (pin "2") (pinfunction "2_2") (pintype "passive"))
      (node (ref "R176") (pin "1") (pinfunction "1_1") (pintype "passive"))
      (node (ref "R177") (pin "2") (pinfunction "2_2") (pintype "passive"))
    )
    (net (code "193") (name "Net-(R179-Pad2)") (class "Default")
      (node (ref "R179") (pin "2") (pinfunction "2_2") (pintype "passive"))
      (node (ref "R180") (pin "1") (pinfunction "1_1") (pintype "passive"))
    )
    (net (code "194") (name "Net-(R180-Pad2)") (class "Default")
      (node (ref "R180") (pin "2") (pinfunction "2_2") (pintype "passive"))
      (node (ref "R181") (pin "1") (pinfunction "1_1") (pintype "passive"))
    )
    (net (code "195") (name "Net-(R182-Pad1)") (class "Default")
      (node (ref "R182") (pin "1") (pinfunction "1_1") (pintype "passive"))
      (node (ref "R183") (pin "2") (pinfunction "2_2") (pintype "passive"))
    )
    (net (code "196") (name "Net-(R183-Pad1)") (class "Default")
      (node (ref "R183") (pin "1") (pinfunction "1_1") (pintype "passive"))
      (node (ref "R184") (pin "1") (pinfunction "1_1") (pintype "passive"))
    )
    (net (code "197") (name "Net-(R189-Pad2)") (class "Default")
      (node (ref "R189") (pin "2") (pinfunction "2_2") (pintype "passive"))
      (node (ref "R190") (pin "2") (pinfunction "2_2") (pintype "passive"))
      (node (ref "R191") (pin "1") (pinfunction "1_1") (pintype "passive"))
    )
    (net (code "198") (name "Net-(R192-Pad1)") (class "Default")
      (node (ref "R192") (pin "1") (pinfunction "1_1") (pintype "passive"))
      (node (ref "R193") (pin "2") (pinfunction "2_2") (pintype "passive"))
    )
    (net (code "199") (name "Net-(R193-Pad1)") (class "Default")
      (node (ref "R193") (pin "1") (pinfunction "1_1") (pintype "passive"))
      (node (ref "R194") (pin "2") (pinfunction "2_2") (pintype "passive"))
    )
    (net (code "200") (name "Net-(R194-Pad1)") (class "Default")
      (node (ref "R194") (pin "1") (pinfunction "1_1") (pintype "passive"))
      (node (ref "R195") (pin "2") (pinfunction "2_2") (pintype "passive"))
    )
    (net (code "201") (name "Net-(R195-Pad1)") (class "Default")
      (node (ref "R195") (pin "1") (pinfunction "1_1") (pintype "passive"))
      (node (ref "R196") (pin "2") (pinfunction "2_2") (pintype "passive"))
    )
    (net (code "202") (name "Net-(R200-Pad2)") (class "Default")
      (node (ref "R200") (pin "2") (pinfunction "2_2") (pintype "passive"))
      (node (ref "R201") (pin "1") (pinfunction "1_1") (pintype "passive"))
      (node (ref "R202") (pin "2") (pinfunction "2_2") (pintype "passive"))
    )
    (net (code "203") (name "Net-(R204-Pad2)") (class "Default")
      (node (ref "R204") (pin "2") (pinfunction "2_2") (pintype "passive"))
      (node (ref "R205") (pin "1") (pinfunction "1_1") (pintype "passive"))
    )
    (net (code "204") (name "Net-(R205-Pad2)") (class "Default")
      (node (ref "R205") (pin "2") (pinfunction "2_2") (pintype "passive"))
      (node (ref "R206") (pin "1") (pinfunction "1_1") (pintype "passive"))
    )
    (net (code "205") (name "Net-(R207-Pad1)") (class "Default")
      (node (ref "R207") (pin "1") (pinfunction "1_1") (pintype "passive"))
      (node (ref "R208") (pin "2") (pinfunction "2_2") (pintype "passive"))
    )
    (net (code "206") (name "Net-(R208-Pad1)") (class "Default")
      (node (ref "R208") (pin "1") (pinfunction "1_1") (pintype "passive"))
      (node (ref "R209") (pin "1") (pinfunction "1_1") (pintype "passive"))
    )
    (net (code "207") (name "Net-(T1-B)") (class "Default")
      (node (ref "C9") (pin "2") (pinfunction "2_2") (pintype "passive"))
      (node (ref "R12") (pin "1") (pinfunction "1_1") (pintype "passive"))
      (node (ref "T1") (pin "2") (pinfunction "B_2") (pintype "passive"))
    )
    (net (code "208") (name "Net-(T1-C)") (class "Default")
      (node (ref "C9") (pin "1") (pinfunction "1_1") (pintype "passive"))
      (node (ref "R15") (pin "1") (pinfunction "1_1") (pintype "passive"))
      (node (ref "T1") (pin "1") (pinfunction "C_1") (pintype "passive"))
      (node (ref "T2") (pin "2") (pinfunction "B_2") (pintype "passive"))
    )
    (net (code "209") (name "Net-(T2-E)") (class "Default")
      (node (ref "R11") (pin "2") (pinfunction "2_2") (pintype "passive"))
      (node (ref "R12") (pin "2") (pinfunction "2_2") (pintype "passive"))
      (node (ref "T2") (pin "3") (pinfunction "E_3") (pintype "passive"))
    )
    (net (code "210") (name "Net-(U$1-CC1)") (class "Default")
      (node (ref "C10") (pin "1") (pinfunction "1_1") (pintype "passive"))
      (node (ref "U$1") (pin "P$3") (pinfunction "CC1_P$3") (pintype "bidirectional"))
    )
    (net (code "211") (name "Net-(U$1-CC2)") (class "Default")
      (node (ref "C10") (pin "2") (pinfunction "2_2") (pintype "passive"))
      (node (ref "U$1") (pin "P$4") (pinfunction "CC2_P$4") (pintype "bidirectional"))
    )
    (net (code "212") (name "Net-(U$2-CC1)") (class "Default")
      (node (ref "C12") (pin "1") (pinfunction "1_1") (pintype "passive"))
      (node (ref "U$2") (pin "P$3") (pinfunction "CC1_P$3") (pintype "bidirectional"))
    )
    (net (code "213") (name "Net-(U$2-CC2)") (class "Default")
      (node (ref "C12") (pin "2") (pinfunction "2_2") (pintype "passive"))
      (node (ref "U$2") (pin "P$4") (pinfunction "CC2_P$4") (pintype "bidirectional"))
    )
    (net (code "214") (name "Net-(U$3-CC1)") (class "Default")
      (node (ref "C14") (pin "1") (pinfunction "1_1") (pintype "passive"))
      (node (ref "U$3") (pin "P$3") (pinfunction "CC1_P$3") (pintype "bidirectional"))
    )
    (net (code "215") (name "Net-(U$3-CC2)") (class "Default")
      (node (ref "C14") (pin "2") (pinfunction "2_2") (pintype "passive"))
      (node (ref "U$3") (pin "P$4") (pinfunction "CC2_P$4") (pintype "bidirectional"))
    )
    (net (code "216") (name "Net-(U$4-CC1)") (class "Default")
      (node (ref "C5") (pin "1") (pinfunction "1_1") (pintype "passive"))
      (node (ref "U$4") (pin "P$3") (pinfunction "CC1_P$3") (pintype "bidirectional"))
    )
    (net (code "217") (name "Net-(U$4-CC2)") (class "Default")
      (node (ref "C5") (pin "2") (pinfunction "2_2") (pintype "passive"))
      (node (ref "U$4") (pin "P$4") (pinfunction "CC2_P$4") (pintype "bidirectional"))
    )
    (net (code "218") (name "Net-(U$4-OUT)") (class "Default")
      (node (ref "C7") (pin "2") (pinfunction "2_2") (pintype "passive"))
      (node (ref "D8") (pin "A") (pinfunction "A_A") (pintype "passive"))
      (node (ref "OUT") (pin "P$1") (pinfunction "P$1_P$1") (pintype "bidirectional"))
      (node (ref "R21") (pin "2") (pinfunction "2_2") (pintype "passive"))
      (node (ref "R3") (pin "2") (pinfunction "2_2") (pintype "passive"))
      (node (ref "U$4") (pin "P$5") (pinfunction "OUT_P$5") (pintype "output"))
    )
    (net (code "219") (name "Net-(U$5-CC1)") (class "Default")
      (node (ref "C16") (pin "1") (pinfunction "1_1") (pintype "passive"))
      (node (ref "U$5") (pin "P$3") (pinfunction "CC1_P$3") (pintype "bidirectional"))
    )
    (net (code "220") (name "Net-(U$5-CC2)") (class "Default")
      (node (ref "C16") (pin "2") (pinfunction "2_2") (pintype "passive"))
      (node (ref "U$5") (pin "P$4") (pinfunction "CC2_P$4") (pintype "bidirectional"))
    )
    (net (code "221") (name "Net-(U$6-CC1)") (class "Default")
      (node (ref "C18") (pin "1") (pinfunction "1_1") (pintype "passive"))
      (node (ref "U$6") (pin "P$3") (pinfunction "CC1_P$3") (pintype "bidirectional"))
    )
    (net (code "222") (name "Net-(U$6-CC2)") (class "Default")
      (node (ref "C18") (pin "2") (pinfunction "2_2") (pintype "passive"))
      (node (ref "U$6") (pin "P$4") (pinfunction "CC2_P$4") (pintype "bidirectional"))
    )
    (net (code "223") (name "Net-(U$7-CC1)") (class "Default")
      (node (ref "C20") (pin "1") (pinfunction "1_1") (pintype "passive"))
      (node (ref "U$7") (pin "P$3") (pinfunction "CC1_P$3") (pintype "bidirectional"))
    )
    (net (code "224") (name "Net-(U$7-CC2)") (class "Default")
      (node (ref "C20") (pin "2") (pinfunction "2_2") (pintype "passive"))
      (node (ref "U$7") (pin "P$4") (pinfunction "CC2_P$4") (pintype "bidirectional"))
    )
    (net (code "225") (name "Net-(U$8-CC1)") (class "Default")
      (node (ref "C22") (pin "1") (pinfunction "1_1") (pintype "passive"))
      (node (ref "U$8") (pin "P$3") (pinfunction "CC1_P$3") (pintype "bidirectional"))
    )
    (net (code "226") (name "Net-(U$8-CC2)") (class "Default")
      (node (ref "C22") (pin "2") (pinfunction "2_2") (pintype "passive"))
      (node (ref "U$8") (pin "P$4") (pinfunction "CC2_P$4") (pintype "bidirectional"))
    )
    (net (code "227") (name "V+") (class "Default")
      (node (ref "C3") (pin "1") (pinfunction "1_1") (pintype "passive"))
      (node (ref "D2") (pin "C") (pinfunction "C_C") (pintype "passive"))
      (node (ref "HVIN") (pin "P$4") (pinfunction "S_P$4") (pintype "passive"))
      (node (ref "Q2") (pin "3") (pinfunction "E_3") (pintype "passive"))
      (node (ref "R8") (pin "2") (pinfunction "2_2") (pintype "passive"))
    )
    (net (code "228") (name "V-") (class "Default")
      (node (ref "C4") (pin "1") (pinfunction "1_1") (pintype "passive"))
      (node (ref "D3") (pin "A") (pinfunction "A_A") (pintype "passive"))
      (node (ref "HVIN") (pin "P$3") (pinfunction "S_P$3") (pintype "passive"))
      (node (ref "R11") (pin "1") (pinfunction "1_1") (pintype "passive"))
      (node (ref "T1") (pin "3") (pinfunction "E_3") (pintype "passive"))
    )
    (net (code "229") (name "unconnected-(J23B-S-PadP$2)") (class "Default")
      (node (ref "J23") (pin "P$2") (pinfunction "S_P$2") (pintype "passive"))
    )
  )
)
